# reaction_wheel_board_2017_12_11.net
KiCad netlist of a schematic drawn in EAGLE
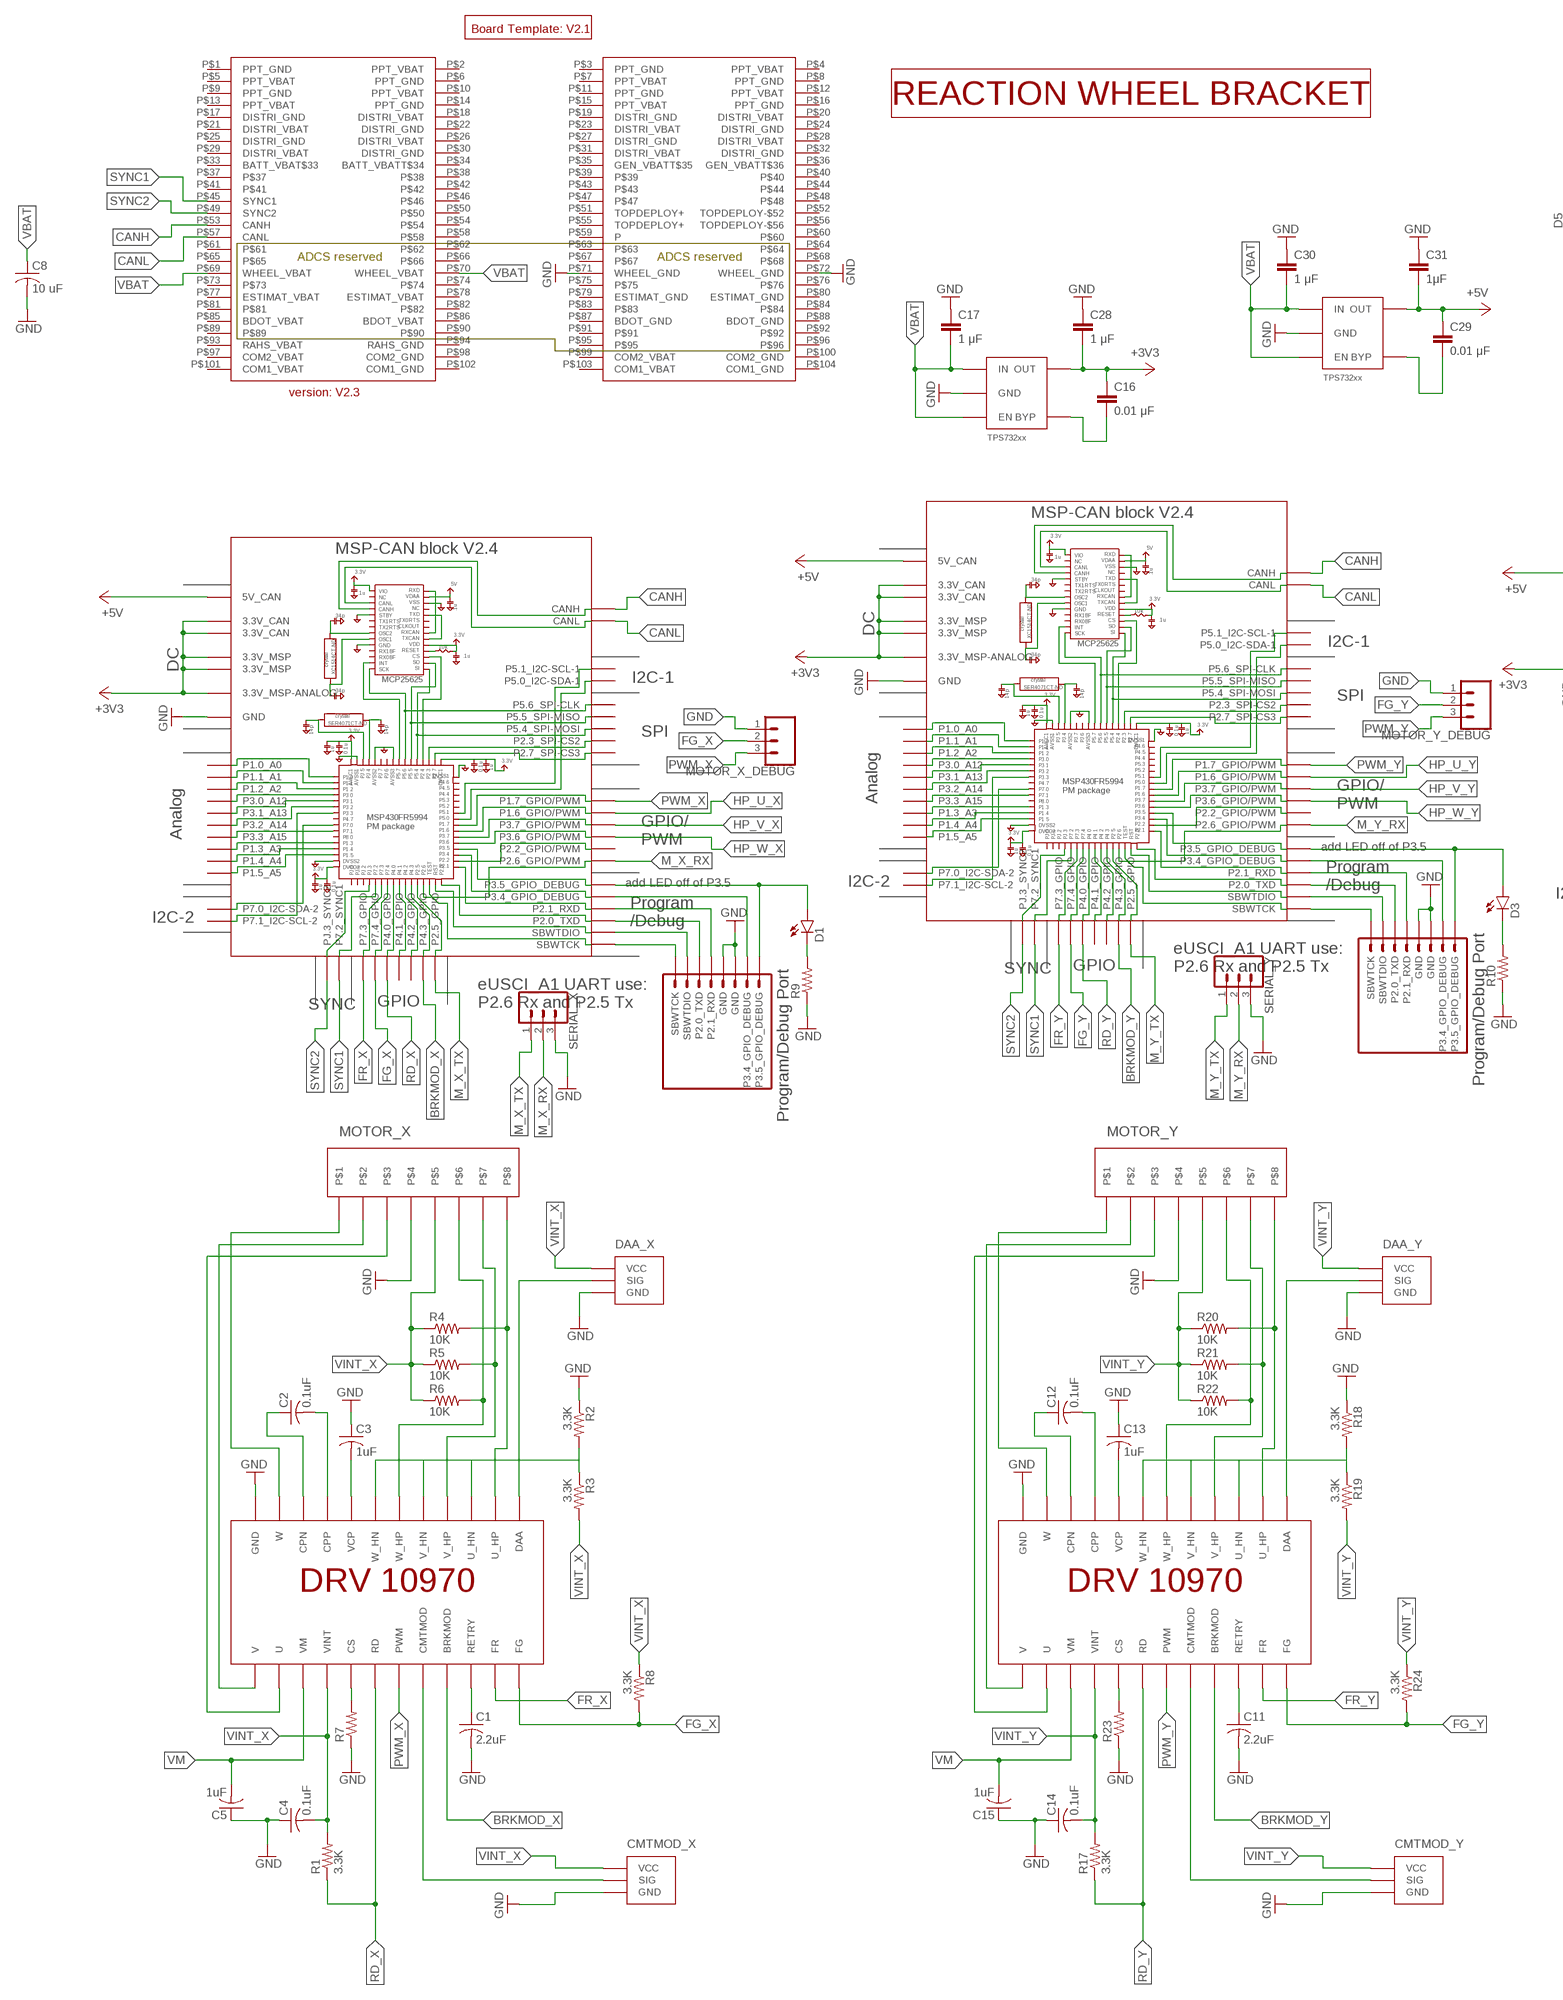
[diagram p0: schematic, sheet 1, part 1 of 2]
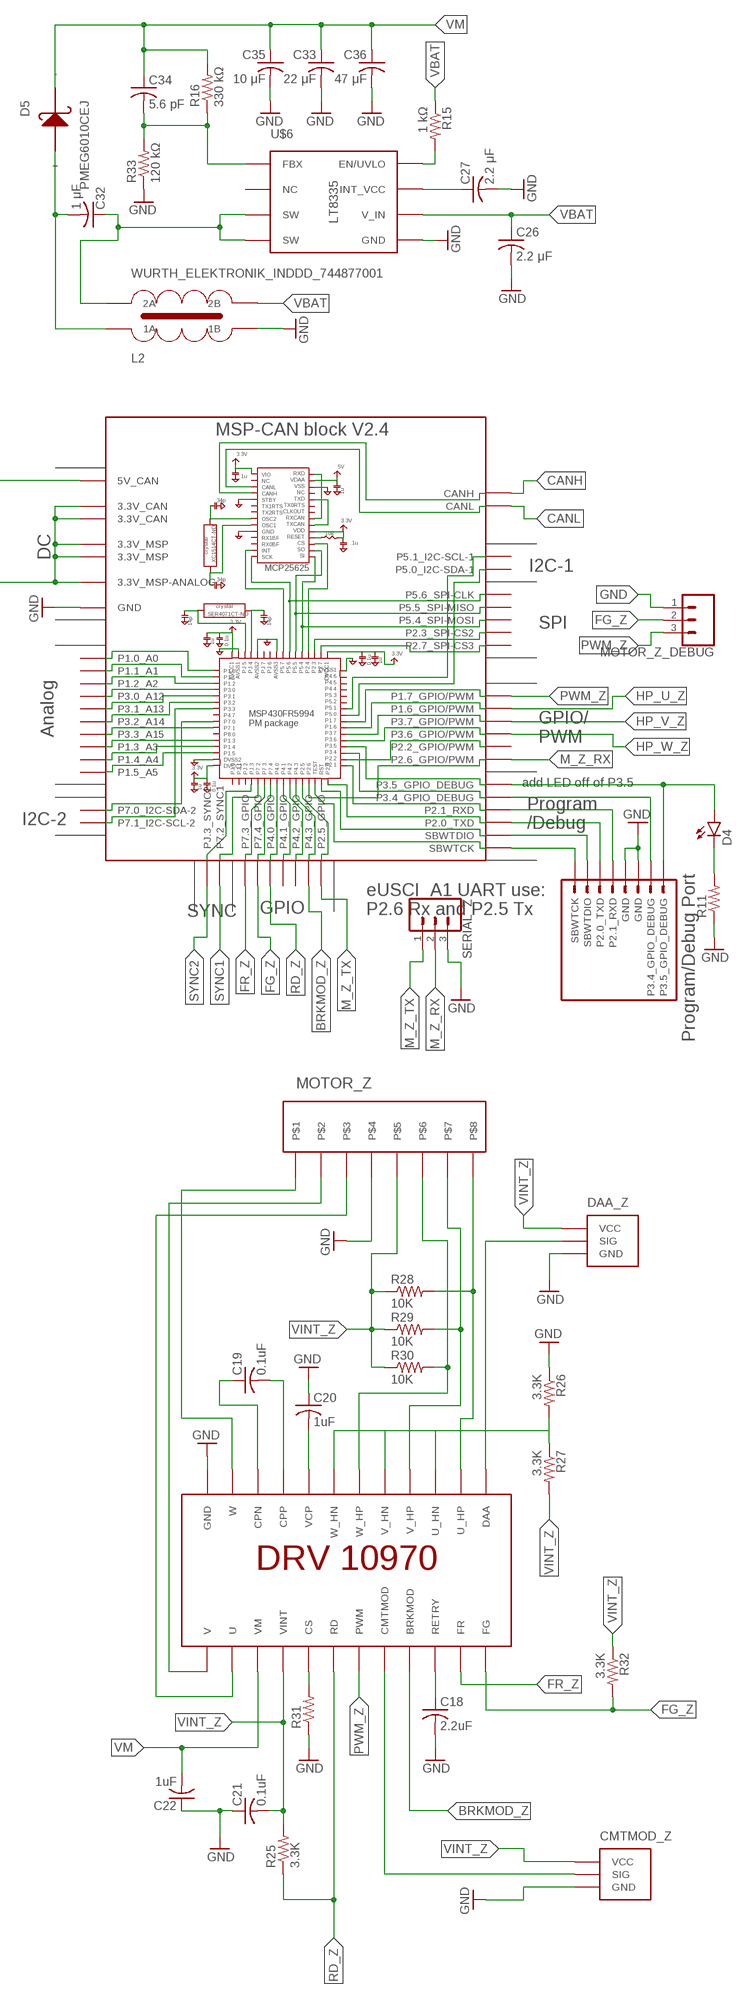
[diagram p1: schematic, sheet 1, part 2 of 2]

(export (version "E")
  (design (tool "Eeschema 10.0.6"))
  (components
    (comp (ref "C1")
      (value "2.2uF")
      (footprint "eagle-import:C1206")
      (libsource (lib "eagle-import") (part "C-USC1206"))
    )
    (comp (ref "C2")
      (value "0.1uF")
      (footprint "eagle-import:C0805")
      (libsource (lib "eagle-import") (part "C-USC0805"))
    )
    (comp (ref "C3")
      (value "1uF")
      (footprint "eagle-import:C1206")
      (libsource (lib "eagle-import") (part "C-USC1206"))
    )
    (comp (ref "C4")
      (value "0.1uF")
      (footprint "eagle-import:C0805")
      (libsource (lib "eagle-import") (part "C-USC0805"))
    )
    (comp (ref "C5")
      (value "1uF")
      (footprint "eagle-import:C1206")
      (libsource (lib "eagle-import") (part "C-USC1206"))
    )
    (comp (ref "C8")
      (value "10 uF")
      (footprint "eagle-import:C0805")
      (libsource (lib "eagle-import") (part "C-USC0805"))
    )
    (comp (ref "C11")
      (value "2.2uF")
      (footprint "eagle-import:C1206")
      (libsource (lib "eagle-import") (part "C-USC1206"))
    )
    (comp (ref "C12")
      (value "0.1uF")
      (footprint "eagle-import:C0805")
      (libsource (lib "eagle-import") (part "C-USC0805"))
    )
    (comp (ref "C13")
      (value "1uF")
      (footprint "eagle-import:C1206")
      (libsource (lib "eagle-import") (part "C-USC1206"))
    )
    (comp (ref "C14")
      (value "0.1uF")
      (footprint "eagle-import:C0805")
      (libsource (lib "eagle-import") (part "C-USC0805"))
    )
    (comp (ref "C15")
      (value "1uF")
      (footprint "eagle-import:C1206")
      (libsource (lib "eagle-import") (part "C-USC1206"))
    )
    (comp (ref "C16")
      (value "0.01 μF")
      (footprint "eagle-import:0805")
      (libsource (lib "eagle-import") (part "CAPACITOR0805"))
    )
    (comp (ref "C17")
      (value "1 μF")
      (footprint "eagle-import:0805")
      (libsource (lib "eagle-import") (part "CAPACITOR0805"))
    )
    (comp (ref "C18")
      (value "2.2uF")
      (footprint "eagle-import:C1206")
      (libsource (lib "eagle-import") (part "C-USC1206"))
    )
    (comp (ref "C19")
      (value "0.1uF")
      (footprint "eagle-import:C0805")
      (libsource (lib "eagle-import") (part "C-USC0805"))
    )
    (comp (ref "C20")
      (value "1uF")
      (footprint "eagle-import:C1206")
      (libsource (lib "eagle-import") (part "C-USC1206"))
    )
    (comp (ref "C21")
      (value "0.1uF")
      (footprint "eagle-import:C0805")
      (libsource (lib "eagle-import") (part "C-USC0805"))
    )
    (comp (ref "C22")
      (value "1uF")
      (footprint "eagle-import:C1206")
      (libsource (lib "eagle-import") (part "C-USC1206"))
    )
    (comp (ref "C26")
      (value "2.2 μF")
      (footprint "eagle-import:C0805")
      (libsource (lib "eagle-import") (part "C-USC0805"))
    )
    (comp (ref "C27")
      (value "2.2 μF")
      (footprint "eagle-import:C0805")
      (libsource (lib "eagle-import") (part "C-USC0805"))
    )
    (comp (ref "C28")
      (value "1 μF")
      (footprint "eagle-import:0805")
      (libsource (lib "eagle-import") (part "CAPACITOR0805"))
    )
    (comp (ref "C29")
      (value "0.01 μF")
      (footprint "eagle-import:0805")
      (libsource (lib "eagle-import") (part "CAPACITOR0805"))
    )
    (comp (ref "C30")
      (value "1 μF")
      (footprint "eagle-import:0805")
      (libsource (lib "eagle-import") (part "CAPACITOR0805"))
    )
    (comp (ref "C31")
      (value "1μF")
      (footprint "eagle-import:0805")
      (libsource (lib "eagle-import") (part "CAPACITOR0805"))
    )
    (comp (ref "C32")
      (value "1 μF")
      (footprint "eagle-import:C0805")
      (libsource (lib "eagle-import") (part "C-USC0805"))
    )
    (comp (ref "C33")
      (value "22 μF")
      (footprint "eagle-import:C1206")
      (libsource (lib "eagle-import") (part "C-USC1206"))
    )
    (comp (ref "C34")
      (value "5.6 pF")
      (footprint "eagle-import:C0805")
      (libsource (lib "eagle-import") (part "C-USC0805"))
    )
    (comp (ref "C35")
      (value "10 μF")
      (footprint "eagle-import:C0805")
      (libsource (lib "eagle-import") (part "C-USC0805"))
    )
    (comp (ref "C36")
      (value "47 μF")
      (footprint "eagle-import:C1206")
      (libsource (lib "eagle-import") (part "C-USC1206"))
    )
    (comp (ref "CMTMOD_X")
      (value "0_OHM_JUMPER")
      (footprint "eagle-import:0_OHM_JUMPER")
      (libsource (lib "eagle-import") (part "0_OHM_JUMPER"))
    )
    (comp (ref "CMTMOD_Y")
      (value "0_OHM_JUMPER")
      (footprint "eagle-import:0_OHM_JUMPER")
      (libsource (lib "eagle-import") (part "0_OHM_JUMPER"))
    )
    (comp (ref "CMTMOD_Z")
      (value "0_OHM_JUMPER")
      (footprint "eagle-import:0_OHM_JUMPER")
      (libsource (lib "eagle-import") (part "0_OHM_JUMPER"))
    )
    (comp (ref "D1")
      (value "LED")
      (footprint "eagle-import:LED-1206")
      (libsource (lib "eagle-import") (part "LED"))
    )
    (comp (ref "D3")
      (value "LED")
      (footprint "eagle-import:LED-1206")
      (libsource (lib "eagle-import") (part "LED"))
    )
    (comp (ref "D4")
      (value "LED")
      (footprint "eagle-import:LED-1206")
      (libsource (lib "eagle-import") (part "LED"))
    )
    (comp (ref "D5")
      (value "PMEG6010CEJ")
      (footprint "eagle-import:SC-90")
      (libsource (lib "eagle-import") (part "PMEG6010CEJ"))
    )
    (comp (ref "DAA_X")
      (value "0_OHM_JUMPER")
      (footprint "eagle-import:0_OHM_JUMPER")
      (libsource (lib "eagle-import") (part "0_OHM_JUMPER"))
    )
    (comp (ref "DAA_Y")
      (value "0_OHM_JUMPER")
      (footprint "eagle-import:0_OHM_JUMPER")
      (libsource (lib "eagle-import") (part "0_OHM_JUMPER"))
    )
    (comp (ref "DAA_Z")
      (value "0_OHM_JUMPER")
      (footprint "eagle-import:0_OHM_JUMPER")
      (libsource (lib "eagle-import") (part "0_OHM_JUMPER"))
    )
    (comp (ref "L2")
      (value "WURTH_ELEKTRONIK_INDDD_744877001")
      (footprint "eagle-import:WURTH_ELEKTRONIK_INDDD_744877001")
      (libsource (lib "eagle-import") (part "WURTH_ELEKTRONIK_INDDD_744877001"))
    )
    (comp (ref "MOTOR_X")
      (value "PICOLOCK_8")
      (footprint "eagle-import:PICOLOCK_8")
      (libsource (lib "eagle-import") (part "PICOLOCK_8"))
    )
    (comp (ref "MOTOR_X_DEBUG")
      (value "CONN_03LOCK")
      (footprint "eagle-import:1X03_LOCK")
      (libsource (lib "eagle-import") (part "CONN_03LOCK"))
    )
    (comp (ref "MOTOR_Y")
      (value "PICOLOCK_8")
      (footprint "eagle-import:PICOLOCK_8")
      (libsource (lib "eagle-import") (part "PICOLOCK_8"))
    )
    (comp (ref "MOTOR_Y_DEBUG")
      (value "CONN_03LOCK")
      (footprint "eagle-import:1X03_LOCK")
      (libsource (lib "eagle-import") (part "CONN_03LOCK"))
    )
    (comp (ref "MOTOR_Z")
      (value "PICOLOCK_8")
      (footprint "eagle-import:PICOLOCK_8")
      (libsource (lib "eagle-import") (part "PICOLOCK_8"))
    )
    (comp (ref "MOTOR_Z_DEBUG")
      (value "CONN_03LOCK")
      (footprint "eagle-import:1X03_LOCK")
      (libsource (lib "eagle-import") (part "CONN_03LOCK"))
    )
    (comp (ref "MSP_X_DEBUG")
      (value "PROGRAM/DEBUG_PORT")
      (footprint "eagle-import:1X08_CONNECTOR")
      (libsource (lib "eagle-import") (part "PROGRAM/DEBUG_PORT"))
    )
    (comp (ref "MSP_Y_DEBUG")
      (value "PROGRAM/DEBUG_PORT")
      (footprint "eagle-import:1X08_CONNECTOR")
      (libsource (lib "eagle-import") (part "PROGRAM/DEBUG_PORT"))
    )
    (comp (ref "MSP_Z_DEBUG")
      (value "PROGRAM/DEBUG_PORT")
      (footprint "eagle-import:1X08_CONNECTOR")
      (libsource (lib "eagle-import") (part "PROGRAM/DEBUG_PORT"))
    )
    (comp (ref "PC104")
      (value "PC104_CONNECTOR")
      (footprint "eagle-import:PC104_CONNECTOR")
      (libsource (lib "eagle-import") (part "PC104_CONNECTOR"))
    )
    (comp (ref "R1")
      (value "3.3K")
      (footprint "eagle-import:0805")
      (libsource (lib "eagle-import") (part "RESISTOR0805"))
    )
    (comp (ref "R2")
      (value "3.3K")
      (footprint "eagle-import:0805")
      (libsource (lib "eagle-import") (part "RESISTOR0805"))
    )
    (comp (ref "R3")
      (value "3.3K")
      (footprint "eagle-import:0805")
      (libsource (lib "eagle-import") (part "RESISTOR0805"))
    )
    (comp (ref "R4")
      (value "10K")
      (footprint "eagle-import:0805")
      (libsource (lib "eagle-import") (part "RESISTOR0805"))
    )
    (comp (ref "R5")
      (value "10K")
      (footprint "eagle-import:0805")
      (libsource (lib "eagle-import") (part "RESISTOR0805"))
    )
    (comp (ref "R6")
      (value "10K")
      (footprint "eagle-import:0805")
      (libsource (lib "eagle-import") (part "RESISTOR0805"))
    )
    (comp (ref "R7")
      (value "RESISTOR0805")
      (footprint "eagle-import:0805")
      (libsource (lib "eagle-import") (part "RESISTOR0805"))
    )
    (comp (ref "R8")
      (value "3.3K")
      (footprint "eagle-import:0805")
      (libsource (lib "eagle-import") (part "RESISTOR0805"))
    )
    (comp (ref "R9")
      (value "RESISTOR0805")
      (footprint "eagle-import:0805")
      (libsource (lib "eagle-import") (part "RESISTOR0805"))
    )
    (comp (ref "R10")
      (value "RESISTOR0805")
      (footprint "eagle-import:0805")
      (libsource (lib "eagle-import") (part "RESISTOR0805"))
    )
    (comp (ref "R11")
      (value "RESISTOR0805")
      (footprint "eagle-import:0805")
      (libsource (lib "eagle-import") (part "RESISTOR0805"))
    )
    (comp (ref "R15")
      (value "1 kΩ")
      (footprint "eagle-import:0805")
      (libsource (lib "eagle-import") (part "RESISTOR0805"))
    )
    (comp (ref "R16")
      (value "330 kΩ")
      (footprint "eagle-import:0805")
      (libsource (lib "eagle-import") (part "RESISTOR0805"))
    )
    (comp (ref "R17")
      (value "3.3K")
      (footprint "eagle-import:0805")
      (libsource (lib "eagle-import") (part "RESISTOR0805"))
    )
    (comp (ref "R18")
      (value "3.3K")
      (footprint "eagle-import:0805")
      (libsource (lib "eagle-import") (part "RESISTOR0805"))
    )
    (comp (ref "R19")
      (value "3.3K")
      (footprint "eagle-import:0805")
      (libsource (lib "eagle-import") (part "RESISTOR0805"))
    )
    (comp (ref "R20")
      (value "10K")
      (footprint "eagle-import:0805")
      (libsource (lib "eagle-import") (part "RESISTOR0805"))
    )
    (comp (ref "R21")
      (value "10K")
      (footprint "eagle-import:0805")
      (libsource (lib "eagle-import") (part "RESISTOR0805"))
    )
    (comp (ref "R22")
      (value "10K")
      (footprint "eagle-import:0805")
      (libsource (lib "eagle-import") (part "RESISTOR0805"))
    )
    (comp (ref "R23")
      (value "RESISTOR0805")
      (footprint "eagle-import:0805")
      (libsource (lib "eagle-import") (part "RESISTOR0805"))
    )
    (comp (ref "R24")
      (value "3.3K")
      (footprint "eagle-import:0805")
      (libsource (lib "eagle-import") (part "RESISTOR0805"))
    )
    (comp (ref "R25")
      (value "3.3K")
      (footprint "eagle-import:0805")
      (libsource (lib "eagle-import") (part "RESISTOR0805"))
    )
    (comp (ref "R26")
      (value "3.3K")
      (footprint "eagle-import:0805")
      (libsource (lib "eagle-import") (part "RESISTOR0805"))
    )
    (comp (ref "R27")
      (value "3.3K")
      (footprint "eagle-import:0805")
      (libsource (lib "eagle-import") (part "RESISTOR0805"))
    )
    (comp (ref "R28")
      (value "10K")
      (footprint "eagle-import:0805")
      (libsource (lib "eagle-import") (part "RESISTOR0805"))
    )
    (comp (ref "R29")
      (value "10K")
      (footprint "eagle-import:0805")
      (libsource (lib "eagle-import") (part "RESISTOR0805"))
    )
    (comp (ref "R30")
      (value "10K")
      (footprint "eagle-import:0805")
      (libsource (lib "eagle-import") (part "RESISTOR0805"))
    )
    (comp (ref "R31")
      (value "RESISTOR0805")
      (footprint "eagle-import:0805")
      (libsource (lib "eagle-import") (part "RESISTOR0805"))
    )
    (comp (ref "R32")
      (value "3.3K")
      (footprint "eagle-import:0805")
      (libsource (lib "eagle-import") (part "RESISTOR0805"))
    )
    (comp (ref "R33")
      (value "120 kΩ")
      (footprint "eagle-import:0805")
      (libsource (lib "eagle-import") (part "RESISTOR0805"))
    )
    (comp (ref "SERIAL_X")
      (value "CONN_03LOCK")
      (footprint "eagle-import:1X03_LOCK")
      (libsource (lib "eagle-import") (part "CONN_03LOCK"))
    )
    (comp (ref "SERIAL_Y")
      (value "CONN_03LOCK")
      (footprint "eagle-import:1X03_LOCK")
      (libsource (lib "eagle-import") (part "CONN_03LOCK"))
    )
    (comp (ref "SERIAL_Z")
      (value "CONN_03LOCK")
      (footprint "eagle-import:1X03_LOCK")
      (libsource (lib "eagle-import") (part "CONN_03LOCK"))
    )
    (comp (ref "U$1")
      (value "BOARD_TEMPLATESERCURED")
      (footprint "eagle-import:BOARD_TEMPLATE_SECURED")
      (libsource (lib "eagle-import") (part "BOARD_TEMPLATESERCURED"))
    )
    (comp (ref "U$3")
      (value "MSP-CAN_BLOCK")
      (footprint "eagle-import:MSP-CAN_BLOCK")
      (libsource (lib "eagle-import") (part "MSP-CAN_BLOCK"))
    )
    (comp (ref "U$6")
      (value "LT8335")
      (footprint "eagle-import:DDB")
      (libsource (lib "eagle-import") (part "LT8335"))
    )
    (comp (ref "U$7")
      (value "DRV10970")
      (footprint "eagle-import:DRV10970")
      (libsource (lib "eagle-import") (part "DRV10970"))
    )
    (comp (ref "U$9")
      (value "REACTION_WHEEL_BRACKET")
      (footprint "eagle-import:REACTION_WHEEL_BRACKET")
      (libsource (lib "eagle-import") (part "REACTION_WHEEL_BRACKET"))
    )
    (comp (ref "U$10")
      (value "MSP-CAN_BLOCK")
      (footprint "eagle-import:MSP-CAN_BLOCK")
      (libsource (lib "eagle-import") (part "MSP-CAN_BLOCK"))
    )
    (comp (ref "U$12")
      (value "DRV10970")
      (footprint "eagle-import:DRV10970")
      (libsource (lib "eagle-import") (part "DRV10970"))
    )
    (comp (ref "U$13")
      (value "MSP-CAN_BLOCK")
      (footprint "eagle-import:MSP-CAN_BLOCK")
      (libsource (lib "eagle-import") (part "MSP-CAN_BLOCK"))
    )
    (comp (ref "U$15")
      (value "DRV10970")
      (footprint "eagle-import:DRV10970")
      (libsource (lib "eagle-import") (part "DRV10970"))
    )
    (comp (ref "U2")
      (value "TPS732XX")
      (footprint "eagle-import:SOT-23-5")
      (libsource (lib "eagle-import") (part "TPS732XX"))
    )
    (comp (ref "U3")
      (value "TPS732XX")
      (footprint "eagle-import:SOT-23-5")
      (libsource (lib "eagle-import") (part "TPS732XX"))
    )
  )
  (nets
    (net (code "1") (name "+3V3") (class "Default")
      (node (ref "C16") (pin "1") (pinfunction "1_1") (pintype "passive"))
      (node (ref "C28") (pin "2") (pinfunction "2_2") (pintype "passive"))
      (node (ref "U$10") (pin "3.3V@CAN1") (pinfunction "3.3V_CAN_3.3V@CAN1") (pintype "bidirectional"))
      (node (ref "U$10") (pin "3.3V@CAN2") (pinfunction "3.3V_CAN_3.3V@CAN2") (pintype "bidirectional"))
      (node (ref "U$10") (pin "3.3V@MSP1") (pinfunction "3.3V_MSP_3.3V@MSP1") (pintype "bidirectional"))
      (node (ref "U$10") (pin "3.3V@MSP2") (pinfunction "3.3V_MSP_3.3V@MSP2") (pintype "bidirectional"))
      (node (ref "U$10") (pin "3.3V_ANALOG@MSP2") (pinfunction "3.3V_MSP-ANALOG_3.3V_ANALOG@MSP2") (pintype "bidirectional"))
      (node (ref "U$13") (pin "3.3V@CAN1") (pinfunction "3.3V_CAN_3.3V@CAN1") (pintype "bidirectional"))
      (node (ref "U$13") (pin "3.3V@CAN2") (pinfunction "3.3V_CAN_3.3V@CAN2") (pintype "bidirectional"))
      (node (ref "U$13") (pin "3.3V@MSP1") (pinfunction "3.3V_MSP_3.3V@MSP1") (pintype "bidirectional"))
      (node (ref "U$13") (pin "3.3V@MSP2") (pinfunction "3.3V_MSP_3.3V@MSP2") (pintype "bidirectional"))
      (node (ref "U$13") (pin "3.3V_ANALOG@MSP2") (pinfunction "3.3V_MSP-ANALOG_3.3V_ANALOG@MSP2") (pintype "bidirectional"))
      (node (ref "U$3") (pin "3.3V@CAN1") (pinfunction "3.3V_CAN_3.3V@CAN1") (pintype "bidirectional"))
      (node (ref "U$3") (pin "3.3V@CAN2") (pinfunction "3.3V_CAN_3.3V@CAN2") (pintype "bidirectional"))
      (node (ref "U$3") (pin "3.3V@MSP1") (pinfunction "3.3V_MSP_3.3V@MSP1") (pintype "bidirectional"))
      (node (ref "U$3") (pin "3.3V@MSP2") (pinfunction "3.3V_MSP_3.3V@MSP2") (pintype "bidirectional"))
      (node (ref "U$3") (pin "3.3V_ANALOG@MSP2") (pinfunction "3.3V_MSP-ANALOG_3.3V_ANALOG@MSP2") (pintype "bidirectional"))
      (node (ref "U2") (pin "P$5") (pinfunction "OUT_P$5") (pintype "bidirectional"))
    )
    (net (code "2") (name "+5V") (class "Default")
      (node (ref "C29") (pin "1") (pinfunction "1_1") (pintype "passive"))
      (node (ref "C31") (pin "2") (pinfunction "2_2") (pintype "passive"))
      (node (ref "U$10") (pin "5V") (pinfunction "5V_CAN_5V") (pintype "bidirectional"))
      (node (ref "U$13") (pin "5V") (pinfunction "5V_CAN_5V") (pintype "bidirectional"))
      (node (ref "U$3") (pin "5V") (pinfunction "5V_CAN_5V") (pintype "bidirectional"))
      (node (ref "U3") (pin "P$5") (pinfunction "OUT_P$5") (pintype "bidirectional"))
    )
    (net (code "3") (name "BRKMOD_X") (class "Default")
      (node (ref "U$3") (pin "P4.3_GPIO") (pinfunction "P4.3_GPIO_P4.3_GPIO") (pintype "bidirectional"))
      (node (ref "U$7") (pin "BRKMOD") (pinfunction "BRKMOD_BRKMOD") (pintype "bidirectional"))
    )
    (net (code "4") (name "BRKMOD_Y") (class "Default")
      (node (ref "U$10") (pin "P4.3_GPIO") (pinfunction "P4.3_GPIO_P4.3_GPIO") (pintype "bidirectional"))
      (node (ref "U$12") (pin "BRKMOD") (pinfunction "BRKMOD_BRKMOD") (pintype "bidirectional"))
    )
    (net (code "5") (name "BRKMOD_Z") (class "Default")
      (node (ref "U$13") (pin "P4.3_GPIO") (pinfunction "P4.3_GPIO_P4.3_GPIO") (pintype "bidirectional"))
      (node (ref "U$15") (pin "BRKMOD") (pinfunction "BRKMOD_BRKMOD") (pintype "bidirectional"))
    )
    (net (code "6") (name "CANH") (class "Default")
      (node (ref "PC104") (pin "P$53") (pinfunction "CANH_P$53") (pintype "bidirectional"))
      (node (ref "U$10") (pin "CANH") (pinfunction "CANH_CANH") (pintype "bidirectional"))
      (node (ref "U$13") (pin "CANH") (pinfunction "CANH_CANH") (pintype "bidirectional"))
      (node (ref "U$3") (pin "CANH") (pinfunction "CANH_CANH") (pintype "bidirectional"))
    )
    (net (code "7") (name "CANL") (class "Default")
      (node (ref "PC104") (pin "P$57") (pinfunction "CANL_P$57") (pintype "bidirectional"))
      (node (ref "U$10") (pin "CANL") (pinfunction "CANL_CANL") (pintype "bidirectional"))
      (node (ref "U$13") (pin "CANL") (pinfunction "CANL_CANL") (pintype "bidirectional"))
      (node (ref "U$3") (pin "CANL") (pinfunction "CANL_CANL") (pintype "bidirectional"))
    )
    (net (code "8") (name "FG_X") (class "Default")
      (node (ref "MOTOR_X_DEBUG") (pin "2") (pinfunction "2_2") (pintype "passive"))
      (node (ref "R8") (pin "2") (pinfunction "2_2") (pintype "passive"))
      (node (ref "U$3") (pin "P7.4_GPIO") (pinfunction "P7.4_GPIO_P7.4_GPIO") (pintype "bidirectional"))
      (node (ref "U$7") (pin "FG") (pinfunction "FG_FG") (pintype "bidirectional"))
    )
    (net (code "9") (name "FG_Y") (class "Default")
      (node (ref "MOTOR_Y_DEBUG") (pin "2") (pinfunction "2_2") (pintype "passive"))
      (node (ref "R24") (pin "2") (pinfunction "2_2") (pintype "passive"))
      (node (ref "U$10") (pin "P7.4_GPIO") (pinfunction "P7.4_GPIO_P7.4_GPIO") (pintype "bidirectional"))
      (node (ref "U$12") (pin "FG") (pinfunction "FG_FG") (pintype "bidirectional"))
    )
    (net (code "10") (name "FG_Z") (class "Default")
      (node (ref "MOTOR_Z_DEBUG") (pin "2") (pinfunction "2_2") (pintype "passive"))
      (node (ref "R32") (pin "2") (pinfunction "2_2") (pintype "passive"))
      (node (ref "U$13") (pin "P7.4_GPIO") (pinfunction "P7.4_GPIO_P7.4_GPIO") (pintype "bidirectional"))
      (node (ref "U$15") (pin "FG") (pinfunction "FG_FG") (pintype "bidirectional"))
    )
    (net (code "11") (name "FR_X") (class "Default")
      (node (ref "U$3") (pin "P7.3_GPIO") (pinfunction "P7.3_GPIO_P7.3_GPIO") (pintype "bidirectional"))
      (node (ref "U$7") (pin "FR") (pinfunction "FR_FR") (pintype "bidirectional"))
    )
    (net (code "12") (name "FR_Y") (class "Default")
      (node (ref "U$10") (pin "P7.3_GPIO") (pinfunction "P7.3_GPIO_P7.3_GPIO") (pintype "bidirectional"))
      (node (ref "U$12") (pin "FR") (pinfunction "FR_FR") (pintype "bidirectional"))
    )
    (net (code "13") (name "FR_Z") (class "Default")
      (node (ref "U$13") (pin "P7.3_GPIO") (pinfunction "P7.3_GPIO_P7.3_GPIO") (pintype "bidirectional"))
      (node (ref "U$15") (pin "FR") (pinfunction "FR_FR") (pintype "bidirectional"))
    )
    (net (code "14") (name "GND") (class "Default")
      (node (ref "C1") (pin "2") (pinfunction "2_2") (pintype "passive"))
      (node (ref "C11") (pin "2") (pinfunction "2_2") (pintype "passive"))
      (node (ref "C13") (pin "1") (pinfunction "1_1") (pintype "passive"))
      (node (ref "C14") (pin "1") (pinfunction "1_1") (pintype "passive"))
      (node (ref "C15") (pin "1") (pinfunction "1_1") (pintype "passive"))
      (node (ref "C17") (pin "1") (pinfunction "1_1") (pintype "passive"))
      (node (ref "C18") (pin "2") (pinfunction "2_2") (pintype "passive"))
      (node (ref "C20") (pin "1") (pinfunction "1_1") (pintype "passive"))
      (node (ref "C21") (pin "1") (pinfunction "1_1") (pintype "passive"))
      (node (ref "C22") (pin "1") (pinfunction "1_1") (pintype "passive"))
      (node (ref "C26") (pin "2") (pinfunction "2_2") (pintype "passive"))
      (node (ref "C27") (pin "2") (pinfunction "2_2") (pintype "passive"))
      (node (ref "C28") (pin "1") (pinfunction "1_1") (pintype "passive"))
      (node (ref "C3") (pin "1") (pinfunction "1_1") (pintype "passive"))
      (node (ref "C30") (pin "1") (pinfunction "1_1") (pintype "passive"))
      (node (ref "C31") (pin "1") (pinfunction "1_1") (pintype "passive"))
      (node (ref "C33") (pin "2") (pinfunction "2_2") (pintype "passive"))
      (node (ref "C35") (pin "2") (pinfunction "2_2") (pintype "passive"))
      (node (ref "C36") (pin "2") (pinfunction "2_2") (pintype "passive"))
      (node (ref "C4") (pin "1") (pinfunction "1_1") (pintype "passive"))
      (node (ref "C5") (pin "1") (pinfunction "1_1") (pintype "passive"))
      (node (ref "C8") (pin "2") (pinfunction "2_2") (pintype "passive"))
      (node (ref "CMTMOD_X") (pin "P$1") (pinfunction "GND_P$1") (pintype "bidirectional"))
      (node (ref "CMTMOD_Y") (pin "P$1") (pinfunction "GND_P$1") (pintype "bidirectional"))
      (node (ref "CMTMOD_Z") (pin "P$1") (pinfunction "GND_P$1") (pintype "bidirectional"))
      (node (ref "DAA_X") (pin "P$1") (pinfunction "GND_P$1") (pintype "bidirectional"))
      (node (ref "DAA_Y") (pin "P$1") (pinfunction "GND_P$1") (pintype "bidirectional"))
      (node (ref "DAA_Z") (pin "P$1") (pinfunction "GND_P$1") (pintype "bidirectional"))
      (node (ref "L2") (pin "P$2") (pinfunction "1B_P$2") (pintype "bidirectional"))
      (node (ref "MOTOR_X") (pin "P$4") (pinfunction "P$4_P$4") (pintype "bidirectional"))
      (node (ref "MOTOR_X_DEBUG") (pin "1") (pinfunction "1_1") (pintype "passive"))
      (node (ref "MOTOR_Y") (pin "P$4") (pinfunction "P$4_P$4") (pintype "bidirectional"))
      (node (ref "MOTOR_Y_DEBUG") (pin "1") (pinfunction "1_1") (pintype "passive"))
      (node (ref "MOTOR_Z") (pin "P$4") (pinfunction "P$4_P$4") (pintype "bidirectional"))
      (node (ref "MOTOR_Z_DEBUG") (pin "1") (pinfunction "1_1") (pintype "passive"))
      (node (ref "MSP_X_DEBUG") (pin "5") (pinfunction "GND_5") (pintype "bidirectional"))
      (node (ref "MSP_X_DEBUG") (pin "6") (pinfunction "GND_6") (pintype "bidirectional"))
      (node (ref "MSP_Y_DEBUG") (pin "5") (pinfunction "GND_5") (pintype "bidirectional"))
      (node (ref "MSP_Y_DEBUG") (pin "6") (pinfunction "GND_6") (pintype "bidirectional"))
      (node (ref "MSP_Z_DEBUG") (pin "5") (pinfunction "GND_5") (pintype "bidirectional"))
      (node (ref "MSP_Z_DEBUG") (pin "6") (pinfunction "GND_6") (pintype "bidirectional"))
      (node (ref "PC104") (pin "P$71") (pinfunction "WHEEL_GND_P$71") (pintype "bidirectional"))
      (node (ref "PC104") (pin "P$72") (pinfunction "WHEEL_GND_P$72") (pintype "bidirectional"))
      (node (ref "R10") (pin "1") (pinfunction "1_1") (pintype "passive"))
      (node (ref "R11") (pin "1") (pinfunction "1_1") (pintype "passive"))
      (node (ref "R18") (pin "1") (pinfunction "1_1") (pintype "passive"))
      (node (ref "R2") (pin "1") (pinfunction "1_1") (pintype "passive"))
      (node (ref "R23") (pin "1") (pinfunction "1_1") (pintype "passive"))
      (node (ref "R26") (pin "1") (pinfunction "1_1") (pintype "passive"))
      (node (ref "R31") (pin "1") (pinfunction "1_1") (pintype "passive"))
      (node (ref "R33") (pin "1") (pinfunction "1_1") (pintype "passive"))
      (node (ref "R7") (pin "1") (pinfunction "1_1") (pintype "passive"))
      (node (ref "R9") (pin "1") (pinfunction "1_1") (pintype "passive"))
      (node (ref "SERIAL_X") (pin "3") (pinfunction "3_3") (pintype "passive"))
      (node (ref "SERIAL_Y") (pin "3") (pinfunction "3_3") (pintype "passive"))
      (node (ref "SERIAL_Z") (pin "3") (pinfunction "3_3") (pintype "passive"))
      (node (ref "U$10") (pin "GND@1") (pinfunction "GND_GND@1") (pintype "bidirectional"))
      (node (ref "U$10") (pin "GND@10") (pinfunction "GND_GND@10") (pintype "bidirectional"))
      (node (ref "U$10") (pin "GND@11") (pinfunction "GND_GND@11") (pintype "bidirectional"))
      (node (ref "U$10") (pin "GND@12") (pinfunction "GND_GND@12") (pintype "bidirectional"))
      (node (ref "U$10") (pin "GND@13") (pinfunction "GND_GND@13") (pintype "bidirectional"))
      (node (ref "U$10") (pin "GND@14") (pinfunction "GND_GND@14") (pintype "bidirectional"))
      (node (ref "U$10") (pin "GND@15") (pinfunction "GND_GND@15") (pintype "bidirectional"))
      (node (ref "U$10") (pin "GND@16") (pinfunction "GND_GND@16") (pintype "bidirectional"))
      (node (ref "U$10") (pin "GND@17") (pinfunction "GND_GND@17") (pintype "bidirectional"))
      (node (ref "U$10") (pin "GND@2") (pinfunction "GND_GND@2") (pintype "bidirectional"))
      (node (ref "U$10") (pin "GND@26") (pinfunction "GND_GND@26") (pintype "bidirectional"))
      (node (ref "U$10") (pin "GND@3") (pinfunction "GND_GND@3") (pintype "bidirectional"))
      (node (ref "U$10") (pin "GND@4") (pinfunction "GND_GND@4") (pintype "bidirectional"))
      (node (ref "U$10") (pin "GND@5") (pinfunction "GND_GND@5") (pintype "bidirectional"))
      (node (ref "U$10") (pin "GND@7") (pinfunction "GND_GND@7") (pintype "bidirectional"))
      (node (ref "U$10") (pin "GND@8") (pinfunction "GND_GND@8") (pintype "bidirectional"))
      (node (ref "U$10") (pin "GND@9") (pinfunction "GND_GND@9") (pintype "bidirectional"))
      (node (ref "U$12") (pin "GND@1") (pinfunction "GND_GND@1") (pintype "bidirectional"))
      (node (ref "U$12") (pin "GND@2") (pinfunction "GND_GND@2") (pintype "bidirectional"))
      (node (ref "U$13") (pin "GND@1") (pinfunction "GND_GND@1") (pintype "bidirectional"))
      (node (ref "U$13") (pin "GND@10") (pinfunction "GND_GND@10") (pintype "bidirectional"))
      (node (ref "U$13") (pin "GND@11") (pinfunction "GND_GND@11") (pintype "bidirectional"))
      (node (ref "U$13") (pin "GND@12") (pinfunction "GND_GND@12") (pintype "bidirectional"))
      (node (ref "U$13") (pin "GND@13") (pinfunction "GND_GND@13") (pintype "bidirectional"))
      (node (ref "U$13") (pin "GND@14") (pinfunction "GND_GND@14") (pintype "bidirectional"))
      (node (ref "U$13") (pin "GND@15") (pinfunction "GND_GND@15") (pintype "bidirectional"))
      (node (ref "U$13") (pin "GND@16") (pinfunction "GND_GND@16") (pintype "bidirectional"))
      (node (ref "U$13") (pin "GND@17") (pinfunction "GND_GND@17") (pintype "bidirectional"))
      (node (ref "U$13") (pin "GND@2") (pinfunction "GND_GND@2") (pintype "bidirectional"))
      (node (ref "U$13") (pin "GND@26") (pinfunction "GND_GND@26") (pintype "bidirectional"))
      (node (ref "U$13") (pin "GND@3") (pinfunction "GND_GND@3") (pintype "bidirectional"))
      (node (ref "U$13") (pin "GND@4") (pinfunction "GND_GND@4") (pintype "bidirectional"))
      (node (ref "U$13") (pin "GND@5") (pinfunction "GND_GND@5") (pintype "bidirectional"))
      (node (ref "U$13") (pin "GND@7") (pinfunction "GND_GND@7") (pintype "bidirectional"))
      (node (ref "U$13") (pin "GND@8") (pinfunction "GND_GND@8") (pintype "bidirectional"))
      (node (ref "U$13") (pin "GND@9") (pinfunction "GND_GND@9") (pintype "bidirectional"))
      (node (ref "U$15") (pin "GND@1") (pinfunction "GND_GND@1") (pintype "bidirectional"))
      (node (ref "U$15") (pin "GND@2") (pinfunction "GND_GND@2") (pintype "bidirectional"))
      (node (ref "U$3") (pin "GND@1") (pinfunction "GND_GND@1") (pintype "bidirectional"))
      (node (ref "U$3") (pin "GND@10") (pinfunction "GND_GND@10") (pintype "bidirectional"))
      (node (ref "U$3") (pin "GND@11") (pinfunction "GND_GND@11") (pintype "bidirectional"))
      (node (ref "U$3") (pin "GND@12") (pinfunction "GND_GND@12") (pintype "bidirectional"))
      (node (ref "U$3") (pin "GND@13") (pinfunction "GND_GND@13") (pintype "bidirectional"))
      (node (ref "U$3") (pin "GND@14") (pinfunction "GND_GND@14") (pintype "bidirectional"))
      (node (ref "U$3") (pin "GND@15") (pinfunction "GND_GND@15") (pintype "bidirectional"))
      (node (ref "U$3") (pin "GND@16") (pinfunction "GND_GND@16") (pintype "bidirectional"))
      (node (ref "U$3") (pin "GND@17") (pinfunction "GND_GND@17") (pintype "bidirectional"))
      (node (ref "U$3") (pin "GND@2") (pinfunction "GND_GND@2") (pintype "bidirectional"))
      (node (ref "U$3") (pin "GND@26") (pinfunction "GND_GND@26") (pintype "bidirectional"))
      (node (ref "U$3") (pin "GND@3") (pinfunction "GND_GND@3") (pintype "bidirectional"))
      (node (ref "U$3") (pin "GND@4") (pinfunction "GND_GND@4") (pintype "bidirectional"))
      (node (ref "U$3") (pin "GND@5") (pinfunction "GND_GND@5") (pintype "bidirectional"))
      (node (ref "U$3") (pin "GND@7") (pinfunction "GND_GND@7") (pintype "bidirectional"))
      (node (ref "U$3") (pin "GND@8") (pinfunction "GND_GND@8") (pintype "bidirectional"))
      (node (ref "U$3") (pin "GND@9") (pinfunction "GND_GND@9") (pintype "bidirectional"))
      (node (ref "U$6") (pin "GND") (pinfunction "GND_GND") (pintype "bidirectional"))
      (node (ref "U$6") (pin "P$5") (pinfunction "GND_P$5") (pintype "bidirectional"))
      (node (ref "U$7") (pin "GND@1") (pinfunction "GND_GND@1") (pintype "bidirectional"))
      (node (ref "U$7") (pin "GND@2") (pinfunction "GND_GND@2") (pintype "bidirectional"))
      (node (ref "U2") (pin "P$2") (pinfunction "GND_P$2") (pintype "bidirectional"))
      (node (ref "U3") (pin "P$2") (pinfunction "GND_P$2") (pintype "bidirectional"))
    )
    (net (code "15") (name "HP_U_X") (class "Default")
      (node (ref "MOTOR_X") (pin "P$8") (pinfunction "P$8_P$8") (pintype "bidirectional"))
      (node (ref "R4") (pin "2") (pinfunction "2_2") (pintype "passive"))
      (node (ref "U$3") (pin "P1.6_GPIO/PWM") (pinfunction "P1.6_GPIO/PWM_P1.6_GPIO/PWM") (pintype "bidirectional"))
      (node (ref "U$7") (pin "U_HP") (pinfunction "U_HP_U_HP") (pintype "bidirectional"))
    )
    (net (code "16") (name "HP_U_Y") (class "Default")
      (node (ref "MOTOR_Y") (pin "P$8") (pinfunction "P$8_P$8") (pintype "bidirectional"))
      (node (ref "R20") (pin "2") (pinfunction "2_2") (pintype "passive"))
      (node (ref "U$10") (pin "P1.6_GPIO/PWM") (pinfunction "P1.6_GPIO/PWM_P1.6_GPIO/PWM") (pintype "bidirectional"))
      (node (ref "U$12") (pin "U_HP") (pinfunction "U_HP_U_HP") (pintype "bidirectional"))
    )
    (net (code "17") (name "HP_U_Z") (class "Default")
      (node (ref "MOTOR_Z") (pin "P$8") (pinfunction "P$8_P$8") (pintype "bidirectional"))
      (node (ref "R28") (pin "2") (pinfunction "2_2") (pintype "passive"))
      (node (ref "U$13") (pin "P1.6_GPIO/PWM") (pinfunction "P1.6_GPIO/PWM_P1.6_GPIO/PWM") (pintype "bidirectional"))
      (node (ref "U$15") (pin "U_HP") (pinfunction "U_HP_U_HP") (pintype "bidirectional"))
    )
    (net (code "18") (name "HP_V_X") (class "Default")
      (node (ref "MOTOR_X") (pin "P$7") (pinfunction "P$7_P$7") (pintype "bidirectional"))
      (node (ref "R5") (pin "2") (pinfunction "2_2") (pintype "passive"))
      (node (ref "U$3") (pin "P3.7_GPIO/PWM") (pinfunction "P3.7_GPIO/PWM_P3.7_GPIO/PWM") (pintype "bidirectional"))
      (node (ref "U$7") (pin "V_HP") (pinfunction "V_HP_V_HP") (pintype "bidirectional"))
    )
    (net (code "19") (name "HP_V_Y") (class "Default")
      (node (ref "MOTOR_Y") (pin "P$7") (pinfunction "P$7_P$7") (pintype "bidirectional"))
      (node (ref "R21") (pin "2") (pinfunction "2_2") (pintype "passive"))
      (node (ref "U$10") (pin "P3.7_GPIO/PWM") (pinfunction "P3.7_GPIO/PWM_P3.7_GPIO/PWM") (pintype "bidirectional"))
      (node (ref "U$12") (pin "V_HP") (pinfunction "V_HP_V_HP") (pintype "bidirectional"))
    )
    (net (code "20") (name "HP_V_Z") (class "Default")
      (node (ref "MOTOR_Z") (pin "P$7") (pinfunction "P$7_P$7") (pintype "bidirectional"))
      (node (ref "R29") (pin "2") (pinfunction "2_2") (pintype "passive"))
      (node (ref "U$13") (pin "P3.7_GPIO/PWM") (pinfunction "P3.7_GPIO/PWM_P3.7_GPIO/PWM") (pintype "bidirectional"))
      (node (ref "U$15") (pin "V_HP") (pinfunction "V_HP_V_HP") (pintype "bidirectional"))
    )
    (net (code "21") (name "HP_W_X") (class "Default")
      (node (ref "MOTOR_X") (pin "P$6") (pinfunction "P$6_P$6") (pintype "bidirectional"))
      (node (ref "R6") (pin "2") (pinfunction "2_2") (pintype "passive"))
      (node (ref "U$3") (pin "P3.6_GPIO/PWM") (pinfunction "P3.6_GPIO/PWM_P3.6_GPIO/PWM") (pintype "bidirectional"))
      (node (ref "U$7") (pin "W_HP") (pinfunction "W_HP_W_HP") (pintype "bidirectional"))
    )
    (net (code "22") (name "HP_W_Y") (class "Default")
      (node (ref "MOTOR_Y") (pin "P$6") (pinfunction "P$6_P$6") (pintype "bidirectional"))
      (node (ref "R22") (pin "2") (pinfunction "2_2") (pintype "passive"))
      (node (ref "U$10") (pin "P3.6_GPIO/PWM") (pinfunction "P3.6_GPIO/PWM_P3.6_GPIO/PWM") (pintype "bidirectional"))
      (node (ref "U$12") (pin "W_HP") (pinfunction "W_HP_W_HP") (pintype "bidirectional"))
    )
    (net (code "23") (name "HP_W_Z") (class "Default")
      (node (ref "MOTOR_Z") (pin "P$6") (pinfunction "P$6_P$6") (pintype "bidirectional"))
      (node (ref "R30") (pin "2") (pinfunction "2_2") (pintype "passive"))
      (node (ref "U$13") (pin "P3.6_GPIO/PWM") (pinfunction "P3.6_GPIO/PWM_P3.6_GPIO/PWM") (pintype "bidirectional"))
      (node (ref "U$15") (pin "W_HP") (pinfunction "W_HP_W_HP") (pintype "bidirectional"))
    )
    (net (code "24") (name "M_X_RX") (class "Default")
      (node (ref "SERIAL_X") (pin "2") (pinfunction "2_2") (pintype "passive"))
      (node (ref "U$3") (pin "P2.6_GPIO/PWM") (pinfunction "P2.6_GPIO/PWM_P2.6_GPIO/PWM") (pintype "bidirectional"))
    )
    (net (code "25") (name "M_X_TX") (class "Default")
      (node (ref "SERIAL_X") (pin "1") (pinfunction "1_1") (pintype "passive"))
      (node (ref "U$3") (pin "P2.5_GPIO") (pinfunction "P2.5_GPIO_P2.5_GPIO") (pintype "bidirectional"))
    )
    (net (code "26") (name "M_Y_RX") (class "Default")
      (node (ref "SERIAL_Y") (pin "2") (pinfunction "2_2") (pintype "passive"))
      (node (ref "U$10") (pin "P2.6_GPIO/PWM") (pinfunction "P2.6_GPIO/PWM_P2.6_GPIO/PWM") (pintype "bidirectional"))
    )
    (net (code "27") (name "M_Y_TX") (class "Default")
      (node (ref "SERIAL_Y") (pin "1") (pinfunction "1_1") (pintype "passive"))
      (node (ref "U$10") (pin "P2.5_GPIO") (pinfunction "P2.5_GPIO_P2.5_GPIO") (pintype "bidirectional"))
    )
    (net (code "28") (name "M_Z_RX") (class "Default")
      (node (ref "SERIAL_Z") (pin "2") (pinfunction "2_2") (pintype "passive"))
      (node (ref "U$13") (pin "P2.6_GPIO/PWM") (pinfunction "P2.6_GPIO/PWM_P2.6_GPIO/PWM") (pintype "bidirectional"))
    )
    (net (code "29") (name "M_Z_TX") (class "Default")
      (node (ref "SERIAL_Z") (pin "1") (pinfunction "1_1") (pintype "passive"))
      (node (ref "U$13") (pin "P2.5_GPIO") (pinfunction "P2.5_GPIO_P2.5_GPIO") (pintype "bidirectional"))
    )
    (net (code "30") (name "Net-(C1-Pad1)") (class "Default")
      (node (ref "C1") (pin "1") (pinfunction "1_1") (pintype "passive"))
      (node (ref "U$7") (pin "RETRY") (pinfunction "RETRY_RETRY") (pintype "bidirectional"))
    )
    (net (code "31") (name "Net-(C2-Pad1)") (class "Default")
      (node (ref "C2") (pin "1") (pinfunction "1_1") (pintype "passive"))
      (node (ref "U$7") (pin "CPN") (pinfunction "CPN_CPN") (pintype "bidirectional"))
    )
    (net (code "32") (name "Net-(C2-Pad2)") (class "Default")
      (node (ref "C2") (pin "2") (pinfunction "2_2") (pintype "passive"))
      (node (ref "U$7") (pin "CPP") (pinfunction "CPP_CPP") (pintype "bidirectional"))
    )
    (net (code "33") (name "Net-(C3-Pad2)") (class "Default")
      (node (ref "C3") (pin "2") (pinfunction "2_2") (pintype "passive"))
      (node (ref "U$7") (pin "VCP") (pinfunction "VCP_VCP") (pintype "bidirectional"))
    )
    (net (code "34") (name "Net-(C11-Pad1)") (class "Default")
      (node (ref "C11") (pin "1") (pinfunction "1_1") (pintype "passive"))
      (node (ref "U$12") (pin "RETRY") (pinfunction "RETRY_RETRY") (pintype "bidirectional"))
    )
    (net (code "35") (name "Net-(C12-Pad1)") (class "Default")
      (node (ref "C12") (pin "1") (pinfunction "1_1") (pintype "passive"))
      (node (ref "U$12") (pin "CPN") (pinfunction "CPN_CPN") (pintype "bidirectional"))
    )
    (net (code "36") (name "Net-(C12-Pad2)") (class "Default")
      (node (ref "C12") (pin "2") (pinfunction "2_2") (pintype "passive"))
      (node (ref "U$12") (pin "CPP") (pinfunction "CPP_CPP") (pintype "bidirectional"))
    )
    (net (code "37") (name "Net-(C13-Pad2)") (class "Default")
      (node (ref "C13") (pin "2") (pinfunction "2_2") (pintype "passive"))
      (node (ref "U$12") (pin "VCP") (pinfunction "VCP_VCP") (pintype "bidirectional"))
    )
    (net (code "38") (name "Net-(C18-Pad1)") (class "Default")
      (node (ref "C18") (pin "1") (pinfunction "1_1") (pintype "passive"))
      (node (ref "U$15") (pin "RETRY") (pinfunction "RETRY_RETRY") (pintype "bidirectional"))
    )
    (net (code "39") (name "Net-(C19-Pad1)") (class "Default")
      (node (ref "C19") (pin "1") (pinfunction "1_1") (pintype "passive"))
      (node (ref "U$15") (pin "CPN") (pinfunction "CPN_CPN") (pintype "bidirectional"))
    )
    (net (code "40") (name "Net-(C19-Pad2)") (class "Default")
      (node (ref "C19") (pin "2") (pinfunction "2_2") (pintype "passive"))
      (node (ref "U$15") (pin "CPP") (pinfunction "CPP_CPP") (pintype "bidirectional"))
    )
    (net (code "41") (name "Net-(C20-Pad2)") (class "Default")
      (node (ref "C20") (pin "2") (pinfunction "2_2") (pintype "passive"))
      (node (ref "U$15") (pin "VCP") (pinfunction "VCP_VCP") (pintype "bidirectional"))
    )
    (net (code "42") (name "Net-(CMTMOD_X-SIG)") (class "Default")
      (node (ref "CMTMOD_X") (pin "P$2") (pinfunction "SIG_P$2") (pintype "bidirectional"))
      (node (ref "U$7") (pin "CMTMOD") (pinfunction "CMTMOD_CMTMOD") (pintype "bidirectional"))
    )
    (net (code "43") (name "Net-(CMTMOD_Y-SIG)") (class "Default")
      (node (ref "CMTMOD_Y") (pin "P$2") (pinfunction "SIG_P$2") (pintype "bidirectional"))
      (node (ref "U$12") (pin "CMTMOD") (pinfunction "CMTMOD_CMTMOD") (pintype "bidirectional"))
    )
    (net (code "44") (name "Net-(CMTMOD_Z-SIG)") (class "Default")
      (node (ref "CMTMOD_Z") (pin "P$2") (pinfunction "SIG_P$2") (pintype "bidirectional"))
      (node (ref "U$15") (pin "CMTMOD") (pinfunction "CMTMOD_CMTMOD") (pintype "bidirectional"))
    )
    (net (code "45") (name "Net-(D1-PadC)") (class "Default")
      (node (ref "D1") (pin "C") (pinfunction "C_C") (pintype "passive"))
      (node (ref "R9") (pin "2") (pinfunction "2_2") (pintype "passive"))
    )
    (net (code "46") (name "Net-(D3-PadC)") (class "Default")
      (node (ref "D3") (pin "C") (pinfunction "C_C") (pintype "passive"))
      (node (ref "R10") (pin "2") (pinfunction "2_2") (pintype "passive"))
    )
    (net (code "47") (name "Net-(D4-PadC)") (class "Default")
      (node (ref "D4") (pin "C") (pinfunction "C_C") (pintype "passive"))
      (node (ref "R11") (pin "2") (pinfunction "2_2") (pintype "passive"))
    )
    (net (code "48") (name "Net-(D5-+)") (class "Default")
      (node (ref "C32") (pin "2") (pinfunction "2_2") (pintype "passive"))
      (node (ref "D5") (pin "P$1") (pinfunction "+_P$1") (pintype "bidirectional"))
      (node (ref "L2") (pin "P$1") (pinfunction "1A_P$1") (pintype "bidirectional"))
    )
    (net (code "49") (name "Net-(DAA_X-SIG)") (class "Default")
      (node (ref "DAA_X") (pin "P$2") (pinfunction "SIG_P$2") (pintype "bidirectional"))
      (node (ref "U$7") (pin "DAA") (pinfunction "DAA_DAA") (pintype "bidirectional"))
    )
    (net (code "50") (name "Net-(DAA_Y-SIG)") (class "Default")
      (node (ref "DAA_Y") (pin "P$2") (pinfunction "SIG_P$2") (pintype "bidirectional"))
      (node (ref "U$12") (pin "DAA") (pinfunction "DAA_DAA") (pintype "bidirectional"))
    )
    (net (code "51") (name "Net-(DAA_Z-SIG)") (class "Default")
      (node (ref "DAA_Z") (pin "P$2") (pinfunction "SIG_P$2") (pintype "bidirectional"))
      (node (ref "U$15") (pin "DAA") (pinfunction "DAA_DAA") (pintype "bidirectional"))
    )
    (net (code "52") (name "Net-(L2-2A)") (class "Default")
      (node (ref "C32") (pin "1") (pinfunction "1_1") (pintype "passive"))
      (node (ref "L2") (pin "P$3") (pinfunction "2A_P$3") (pintype "bidirectional"))
      (node (ref "U$6") (pin "P$3") (pinfunction "SW_P$3") (pintype "bidirectional"))
      (node (ref "U$6") (pin "P$4") (pinfunction "SW_P$4") (pintype "bidirectional"))
    )
    (net (code "53") (name "Net-(MOTOR_X-PadP$1)") (class "Default")
      (node (ref "MOTOR_X") (pin "P$1") (pinfunction "P$1_P$1") (pintype "bidirectional"))
      (node (ref "U$7") (pin "W") (pinfunction "W_W") (pintype "bidirectional"))
    )
    (net (code "54") (name "Net-(MOTOR_X-PadP$2)") (class "Default")
      (node (ref "MOTOR_X") (pin "P$2") (pinfunction "P$2_P$2") (pintype "bidirectional"))
      (node (ref "U$7") (pin "V") (pinfunction "V_V") (pintype "bidirectional"))
    )
    (net (code "55") (name "Net-(MOTOR_X-PadP$3)") (class "Default")
      (node (ref "MOTOR_X") (pin "P$3") (pinfunction "P$3_P$3") (pintype "bidirectional"))
      (node (ref "U$7") (pin "U") (pinfunction "U_U") (pintype "bidirectional"))
    )
    (net (code "56") (name "Net-(MOTOR_Y-PadP$1)") (class "Default")
      (node (ref "MOTOR_Y") (pin "P$1") (pinfunction "P$1_P$1") (pintype "bidirectional"))
      (node (ref "U$12") (pin "W") (pinfunction "W_W") (pintype "bidirectional"))
    )
    (net (code "57") (name "Net-(MOTOR_Y-PadP$2)") (class "Default")
      (node (ref "MOTOR_Y") (pin "P$2") (pinfunction "P$2_P$2") (pintype "bidirectional"))
      (node (ref "U$12") (pin "V") (pinfunction "V_V") (pintype "bidirectional"))
    )
    (net (code "58") (name "Net-(MOTOR_Y-PadP$3)") (class "Default")
      (node (ref "MOTOR_Y") (pin "P$3") (pinfunction "P$3_P$3") (pintype "bidirectional"))
      (node (ref "U$12") (pin "U") (pinfunction "U_U") (pintype "bidirectional"))
    )
    (net (code "59") (name "Net-(MOTOR_Z-PadP$1)") (class "Default")
      (node (ref "MOTOR_Z") (pin "P$1") (pinfunction "P$1_P$1") (pintype "bidirectional"))
      (node (ref "U$15") (pin "W") (pinfunction "W_W") (pintype "bidirectional"))
    )
    (net (code "60") (name "Net-(MOTOR_Z-PadP$2)") (class "Default")
      (node (ref "MOTOR_Z") (pin "P$2") (pinfunction "P$2_P$2") (pintype "bidirectional"))
      (node (ref "U$15") (pin "V") (pinfunction "V_V") (pintype "bidirectional"))
    )
    (net (code "61") (name "Net-(MOTOR_Z-PadP$3)") (class "Default")
      (node (ref "MOTOR_Z") (pin "P$3") (pinfunction "P$3_P$3") (pintype "bidirectional"))
      (node (ref "U$15") (pin "U") (pinfunction "U_U") (pintype "bidirectional"))
    )
    (net (code "62") (name "Net-(MSP_X_DEBUG-P2.0_TXD)") (class "Default")
      (node (ref "MSP_X_DEBUG") (pin "3") (pinfunction "P2.0_TXD_3") (pintype "bidirectional"))
      (node (ref "U$3") (pin "P2.0_TXD") (pinfunction "P2.0_TXD_P2.0_TXD") (pintype "bidirectional"))
    )
    (net (code "63") (name "Net-(MSP_X_DEBUG-P2.1_RXD)") (class "Default")
      (node (ref "MSP_X_DEBUG") (pin "4") (pinfunction "P2.1_RXD_4") (pintype "bidirectional"))
      (node (ref "U$3") (pin "P2.1_RXD") (pinfunction "P2.1_RXD_P2.1_RXD") (pintype "bidirectional"))
    )
    (net (code "64") (name "Net-(MSP_X_DEBUG-P3.4_GPIO_DEBUG)") (class "Default")
      (node (ref "MSP_X_DEBUG") (pin "7") (pinfunction "P3.4_GPIO_DEBUG_7") (pintype "bidirectional"))
      (node (ref "U$3") (pin "P3.4_GPIO_DEBUG") (pinfunction "P3.4_GPIO_DEBUG_P3.4_GPIO_DEBUG") (pintype "bidirectional"))
    )
    (net (code "65") (name "Net-(MSP_X_DEBUG-P3.5_GPIO_DEBUG)") (class "Default")
      (node (ref "D1") (pin "A") (pinfunction "A_A") (pintype "passive"))
      (node (ref "MSP_X_DEBUG") (pin "8") (pinfunction "P3.5_GPIO_DEBUG_8") (pintype "bidirectional"))
      (node (ref "U$3") (pin "P3.5_GPIO_DEBUG") (pinfunction "P3.5_GPIO_DEBUG_P3.5_GPIO_DEBUG") (pintype "bidirectional"))
    )
    (net (code "66") (name "Net-(MSP_X_DEBUG-PadSBWTCK)") (class "Default")
      (node (ref "MSP_X_DEBUG") (pin "SBWTCK") (pinfunction "SBWTCK_SBWTCK") (pintype "bidirectional"))
      (node (ref "U$3") (pin "SBWTCK") (pinfunction "SBWTCK_SBWTCK") (pintype "bidirectional"))
    )
    (net (code "67") (name "Net-(MSP_X_DEBUG-SBWTDIO)") (class "Default")
      (node (ref "MSP_X_DEBUG") (pin "2") (pinfunction "SBWTDIO_2") (pintype "bidirectional"))
      (node (ref "U$3") (pin "SBWTDIO") (pinfunction "SBWTDIO_SBWTDIO") (pintype "bidirectional"))
    )
    (net (code "68") (name "Net-(MSP_Y_DEBUG-P2.0_TXD)") (class "Default")
      (node (ref "MSP_Y_DEBUG") (pin "3") (pinfunction "P2.0_TXD_3") (pintype "bidirectional"))
      (node (ref "U$10") (pin "P2.0_TXD") (pinfunction "P2.0_TXD_P2.0_TXD") (pintype "bidirectional"))
    )
    (net (code "69") (name "Net-(MSP_Y_DEBUG-P2.1_RXD)") (class "Default")
      (node (ref "MSP_Y_DEBUG") (pin "4") (pinfunction "P2.1_RXD_4") (pintype "bidirectional"))
      (node (ref "U$10") (pin "P2.1_RXD") (pinfunction "P2.1_RXD_P2.1_RXD") (pintype "bidirectional"))
    )
    (net (code "70") (name "Net-(MSP_Y_DEBUG-P3.4_GPIO_DEBUG)") (class "Default")
      (node (ref "MSP_Y_DEBUG") (pin "7") (pinfunction "P3.4_GPIO_DEBUG_7") (pintype "bidirectional"))
      (node (ref "U$10") (pin "P3.4_GPIO_DEBUG") (pinfunction "P3.4_GPIO_DEBUG_P3.4_GPIO_DEBUG") (pintype "bidirectional"))
    )
    (net (code "71") (name "Net-(MSP_Y_DEBUG-P3.5_GPIO_DEBUG)") (class "Default")
      (node (ref "D3") (pin "A") (pinfunction "A_A") (pintype "passive"))
      (node (ref "MSP_Y_DEBUG") (pin "8") (pinfunction "P3.5_GPIO_DEBUG_8") (pintype "bidirectional"))
      (node (ref "U$10") (pin "P3.5_GPIO_DEBUG") (pinfunction "P3.5_GPIO_DEBUG_P3.5_GPIO_DEBUG") (pintype "bidirectional"))
    )
    (net (code "72") (name "Net-(MSP_Y_DEBUG-PadSBWTCK)") (class "Default")
      (node (ref "MSP_Y_DEBUG") (pin "SBWTCK") (pinfunction "SBWTCK_SBWTCK") (pintype "bidirectional"))
      (node (ref "U$10") (pin "SBWTCK") (pinfunction "SBWTCK_SBWTCK") (pintype "bidirectional"))
    )
    (net (code "73") (name "Net-(MSP_Y_DEBUG-SBWTDIO)") (class "Default")
      (node (ref "MSP_Y_DEBUG") (pin "2") (pinfunction "SBWTDIO_2") (pintype "bidirectional"))
      (node (ref "U$10") (pin "SBWTDIO") (pinfunction "SBWTDIO_SBWTDIO") (pintype "bidirectional"))
    )
    (net (code "74") (name "Net-(MSP_Z_DEBUG-P2.0_TXD)") (class "Default")
      (node (ref "MSP_Z_DEBUG") (pin "3") (pinfunction "P2.0_TXD_3") (pintype "bidirectional"))
      (node (ref "U$13") (pin "P2.0_TXD") (pinfunction "P2.0_TXD_P2.0_TXD") (pintype "bidirectional"))
    )
    (net (code "75") (name "Net-(MSP_Z_DEBUG-P2.1_RXD)") (class "Default")
      (node (ref "MSP_Z_DEBUG") (pin "4") (pinfunction "P2.1_RXD_4") (pintype "bidirectional"))
      (node (ref "U$13") (pin "P2.1_RXD") (pinfunction "P2.1_RXD_P2.1_RXD") (pintype "bidirectional"))
    )
    (net (code "76") (name "Net-(MSP_Z_DEBUG-P3.4_GPIO_DEBUG)") (class "Default")
      (node (ref "MSP_Z_DEBUG") (pin "7") (pinfunction "P3.4_GPIO_DEBUG_7") (pintype "bidirectional"))
      (node (ref "U$13") (pin "P3.4_GPIO_DEBUG") (pinfunction "P3.4_GPIO_DEBUG_P3.4_GPIO_DEBUG") (pintype "bidirectional"))
    )
    (net (code "77") (name "Net-(MSP_Z_DEBUG-P3.5_GPIO_DEBUG)") (class "Default")
      (node (ref "D4") (pin "A") (pinfunction "A_A") (pintype "passive"))
      (node (ref "MSP_Z_DEBUG") (pin "8") (pinfunction "P3.5_GPIO_DEBUG_8") (pintype "bidirectional"))
      (node (ref "U$13") (pin "P3.5_GPIO_DEBUG") (pinfunction "P3.5_GPIO_DEBUG_P3.5_GPIO_DEBUG") (pintype "bidirectional"))
    )
    (net (code "78") (name "Net-(MSP_Z_DEBUG-PadSBWTCK)") (class "Default")
      (node (ref "MSP_Z_DEBUG") (pin "SBWTCK") (pinfunction "SBWTCK_SBWTCK") (pintype "bidirectional"))
      (node (ref "U$13") (pin "SBWTCK") (pinfunction "SBWTCK_SBWTCK") (pintype "bidirectional"))
    )
    (net (code "79") (name "Net-(MSP_Z_DEBUG-SBWTDIO)") (class "Default")
      (node (ref "MSP_Z_DEBUG") (pin "2") (pinfunction "SBWTDIO_2") (pintype "bidirectional"))
      (node (ref "U$13") (pin "SBWTDIO") (pinfunction "SBWTDIO_SBWTDIO") (pintype "bidirectional"))
    )
    (net (code "80") (name "Net-(R2-Pad2)") (class "Default")
      (node (ref "R2") (pin "2") (pinfunction "2_2") (pintype "passive"))
      (node (ref "R3") (pin "1") (pinfunction "1_1") (pintype "passive"))
      (node (ref "U$7") (pin "U_HN") (pinfunction "U_HN_U_HN") (pintype "bidirectional"))
      (node (ref "U$7") (pin "V_HN") (pinfunction "V_HN_V_HN") (pintype "bidirectional"))
      (node (ref "U$7") (pin "W_HN") (pinfunction "W_HN_W_HN") (pintype "bidirectional"))
    )
    (net (code "81") (name "Net-(R7-Pad2)") (class "Default")
      (node (ref "R7") (pin "2") (pinfunction "2_2") (pintype "passive"))
      (node (ref "U$7") (pin "CS") (pinfunction "CS_CS") (pintype "bidirectional"))
    )
    (net (code "82") (name "Net-(R18-Pad2)") (class "Default")
      (node (ref "R18") (pin "2") (pinfunction "2_2") (pintype "passive"))
      (node (ref "R19") (pin "1") (pinfunction "1_1") (pintype "passive"))
      (node (ref "U$12") (pin "U_HN") (pinfunction "U_HN_U_HN") (pintype "bidirectional"))
      (node (ref "U$12") (pin "V_HN") (pinfunction "V_HN_V_HN") (pintype "bidirectional"))
      (node (ref "U$12") (pin "W_HN") (pinfunction "W_HN_W_HN") (pintype "bidirectional"))
    )
    (net (code "83") (name "Net-(R23-Pad2)") (class "Default")
      (node (ref "R23") (pin "2") (pinfunction "2_2") (pintype "passive"))
      (node (ref "U$12") (pin "CS") (pinfunction "CS_CS") (pintype "bidirectional"))
    )
    (net (code "84") (name "Net-(R26-Pad2)") (class "Default")
      (node (ref "R26") (pin "2") (pinfunction "2_2") (pintype "passive"))
      (node (ref "R27") (pin "1") (pinfunction "1_1") (pintype "passive"))
      (node (ref "U$15") (pin "U_HN") (pinfunction "U_HN_U_HN") (pintype "bidirectional"))
      (node (ref "U$15") (pin "V_HN") (pinfunction "V_HN_V_HN") (pintype "bidirectional"))
      (node (ref "U$15") (pin "W_HN") (pinfunction "W_HN_W_HN") (pintype "bidirectional"))
    )
    (net (code "85") (name "Net-(R31-Pad2)") (class "Default")
      (node (ref "R31") (pin "2") (pinfunction "2_2") (pintype "passive"))
      (node (ref "U$15") (pin "CS") (pinfunction "CS_CS") (pintype "bidirectional"))
    )
    (net (code "86") (name "Net-(U$6-EN{slash}UVLO)") (class "Default")
      (node (ref "R15") (pin "2") (pinfunction "2_2") (pintype "passive"))
      (node (ref "U$6") (pin "P$8") (pinfunction "EN/UVLO_P$8") (pintype "bidirectional"))
    )
    (net (code "87") (name "Net-(U$6-FBX)") (class "Default")
      (node (ref "C34") (pin "2") (pinfunction "2_2") (pintype "passive"))
      (node (ref "R16") (pin "1") (pinfunction "1_1") (pintype "passive"))
      (node (ref "R33") (pin "2") (pinfunction "2_2") (pintype "passive"))
      (node (ref "U$6") (pin "P$1") (pinfunction "FBX_P$1") (pintype "bidirectional"))
    )
    (net (code "88") (name "Net-(U$6-INT_VCC)") (class "Default")
      (node (ref "C27") (pin "1") (pinfunction "1_1") (pintype "passive"))
      (node (ref "U$6") (pin "P$7") (pinfunction "INT_VCC_P$7") (pintype "bidirectional"))
    )
    (net (code "89") (name "Net-(U2-BYP)") (class "Default")
      (node (ref "C16") (pin "2") (pinfunction "2_2") (pintype "passive"))
      (node (ref "U2") (pin "P$4") (pinfunction "BYP_P$4") (pintype "bidirectional"))
    )
    (net (code "90") (name "Net-(U3-BYP)") (class "Default")
      (node (ref "C29") (pin "2") (pinfunction "2_2") (pintype "passive"))
      (node (ref "U3") (pin "P$4") (pinfunction "BYP_P$4") (pintype "bidirectional"))
    )
    (net (code "91") (name "PWM_X") (class "Default")
      (node (ref "MOTOR_X_DEBUG") (pin "3") (pinfunction "3_3") (pintype "passive"))
      (node (ref "U$3") (pin "P1.7_GPIO/PWM") (pinfunction "P1.7_GPIO/PWM_P1.7_GPIO/PWM") (pintype "bidirectional"))
      (node (ref "U$7") (pin "PWM") (pinfunction "PWM_PWM") (pintype "bidirectional"))
    )
    (net (code "92") (name "PWM_Y") (class "Default")
      (node (ref "MOTOR_Y_DEBUG") (pin "3") (pinfunction "3_3") (pintype "passive"))
      (node (ref "U$10") (pin "P1.7_GPIO/PWM") (pinfunction "P1.7_GPIO/PWM_P1.7_GPIO/PWM") (pintype "bidirectional"))
      (node (ref "U$12") (pin "PWM") (pinfunction "PWM_PWM") (pintype "bidirectional"))
    )
    (net (code "93") (name "PWM_Z") (class "Default")
      (node (ref "MOTOR_Z_DEBUG") (pin "3") (pinfunction "3_3") (pintype "passive"))
      (node (ref "U$13") (pin "P1.7_GPIO/PWM") (pinfunction "P1.7_GPIO/PWM_P1.7_GPIO/PWM") (pintype "bidirectional"))
      (node (ref "U$15") (pin "PWM") (pinfunction "PWM_PWM") (pintype "bidirectional"))
    )
    (net (code "94") (name "RD_X") (class "Default")
      (node (ref "R1") (pin "1") (pinfunction "1_1") (pintype "passive"))
      (node (ref "U$3") (pin "P4.0_GPIO") (pinfunction "P4.0_GPIO_P4.0_GPIO") (pintype "bidirectional"))
      (node (ref "U$7") (pin "RD") (pinfunction "RD_RD") (pintype "bidirectional"))
    )
    (net (code "95") (name "RD_Y") (class "Default")
      (node (ref "R17") (pin "1") (pinfunction "1_1") (pintype "passive"))
      (node (ref "U$10") (pin "P4.0_GPIO") (pinfunction "P4.0_GPIO_P4.0_GPIO") (pintype "bidirectional"))
      (node (ref "U$12") (pin "RD") (pinfunction "RD_RD") (pintype "bidirectional"))
    )
    (net (code "96") (name "RD_Z") (class "Default")
      (node (ref "R25") (pin "1") (pinfunction "1_1") (pintype "passive"))
      (node (ref "U$13") (pin "P4.0_GPIO") (pinfunction "P4.0_GPIO_P4.0_GPIO") (pintype "bidirectional"))
      (node (ref "U$15") (pin "RD") (pinfunction "RD_RD") (pintype "bidirectional"))
    )
    (net (code "97") (name "SYNC1") (class "Default")
      (node (ref "PC104") (pin "P$45") (pinfunction "SYNC1_P$45") (pintype "bidirectional"))
      (node (ref "U$10") (pin "P7.2_SYNC1") (pinfunction "P7.2_SYNC1_P7.2_SYNC1") (pintype "bidirectional"))
      (node (ref "U$13") (pin "P7.2_SYNC1") (pinfunction "P7.2_SYNC1_P7.2_SYNC1") (pintype "bidirectional"))
      (node (ref "U$3") (pin "P7.2_SYNC1") (pinfunction "P7.2_SYNC1_P7.2_SYNC1") (pintype "bidirectional"))
    )
    (net (code "98") (name "SYNC2") (class "Default")
      (node (ref "PC104") (pin "P$49") (pinfunction "SYNC2_P$49") (pintype "bidirectional"))
      (node (ref "U$10") (pin "PJ.3_SYNC2") (pinfunction "PJ.3_SYNC2_PJ.3_SYNC2") (pintype "bidirectional"))
      (node (ref "U$13") (pin "PJ.3_SYNC2") (pinfunction "PJ.3_SYNC2_PJ.3_SYNC2") (pintype "bidirectional"))
      (node (ref "U$3") (pin "PJ.3_SYNC2") (pinfunction "PJ.3_SYNC2_PJ.3_SYNC2") (pintype "bidirectional"))
    )
    (net (code "99") (name "VBAT") (class "Default")
      (node (ref "C17") (pin "2") (pinfunction "2_2") (pintype "passive"))
      (node (ref "C26") (pin "1") (pinfunction "1_1") (pintype "passive"))
      (node (ref "C30") (pin "2") (pinfunction "2_2") (pintype "passive"))
      (node (ref "C8") (pin "1") (pinfunction "1_1") (pintype "passive"))
      (node (ref "L2") (pin "P$4") (pinfunction "2B_P$4") (pintype "bidirectional"))
      (node (ref "PC104") (pin "P$69") (pinfunction "WHEEL_VBAT_P$69") (pintype "bidirectional"))
      (node (ref "PC104") (pin "P$70") (pinfunction "WHEEL_VBAT_P$70") (pintype "bidirectional"))
      (node (ref "R15") (pin "1") (pinfunction "1_1") (pintype "passive"))
      (node (ref "U$6") (pin "P$6") (pinfunction "V_IN_P$6") (pintype "bidirectional"))
      (node (ref "U2") (pin "P$1") (pinfunction "IN_P$1") (pintype "bidirectional"))
      (node (ref "U2") (pin "P$3") (pinfunction "EN_P$3") (pintype "bidirectional"))
      (node (ref "U3") (pin "P$1") (pinfunction "IN_P$1") (pintype "bidirectional"))
      (node (ref "U3") (pin "P$3") (pinfunction "EN_P$3") (pintype "bidirectional"))
    )
    (net (code "100") (name "VINT_X") (class "Default")
      (node (ref "C4") (pin "2") (pinfunction "2_2") (pintype "passive"))
      (node (ref "CMTMOD_X") (pin "P$3") (pinfunction "VCC_P$3") (pintype "bidirectional"))
      (node (ref "DAA_X") (pin "P$3") (pinfunction "VCC_P$3") (pintype "bidirectional"))
      (node (ref "MOTOR_X") (pin "P$5") (pinfunction "P$5_P$5") (pintype "bidirectional"))
      (node (ref "R1") (pin "2") (pinfunction "2_2") (pintype "passive"))
      (node (ref "R3") (pin "2") (pinfunction "2_2") (pintype "passive"))
      (node (ref "R4") (pin "1") (pinfunction "1_1") (pintype "passive"))
      (node (ref "R5") (pin "1") (pinfunction "1_1") (pintype "passive"))
      (node (ref "R6") (pin "1") (pinfunction "1_1") (pintype "passive"))
      (node (ref "R8") (pin "1") (pinfunction "1_1") (pintype "passive"))
      (node (ref "U$7") (pin "VINT") (pinfunction "VINT_VINT") (pintype "bidirectional"))
    )
    (net (code "101") (name "VINT_Y") (class "Default")
      (node (ref "C14") (pin "2") (pinfunction "2_2") (pintype "passive"))
      (node (ref "CMTMOD_Y") (pin "P$3") (pinfunction "VCC_P$3") (pintype "bidirectional"))
      (node (ref "DAA_Y") (pin "P$3") (pinfunction "VCC_P$3") (pintype "bidirectional"))
      (node (ref "MOTOR_Y") (pin "P$5") (pinfunction "P$5_P$5") (pintype "bidirectional"))
      (node (ref "R17") (pin "2") (pinfunction "2_2") (pintype "passive"))
      (node (ref "R19") (pin "2") (pinfunction "2_2") (pintype "passive"))
      (node (ref "R20") (pin "1") (pinfunction "1_1") (pintype "passive"))
      (node (ref "R21") (pin "1") (pinfunction "1_1") (pintype "passive"))
      (node (ref "R22") (pin "1") (pinfunction "1_1") (pintype "passive"))
      (node (ref "R24") (pin "1") (pinfunction "1_1") (pintype "passive"))
      (node (ref "U$12") (pin "VINT") (pinfunction "VINT_VINT") (pintype "bidirectional"))
    )
    (net (code "102") (name "VINT_Z") (class "Default")
      (node (ref "C21") (pin "2") (pinfunction "2_2") (pintype "passive"))
      (node (ref "CMTMOD_Z") (pin "P$3") (pinfunction "VCC_P$3") (pintype "bidirectional"))
      (node (ref "DAA_Z") (pin "P$3") (pinfunction "VCC_P$3") (pintype "bidirectional"))
      (node (ref "MOTOR_Z") (pin "P$5") (pinfunction "P$5_P$5") (pintype "bidirectional"))
      (node (ref "R25") (pin "2") (pinfunction "2_2") (pintype "passive"))
      (node (ref "R27") (pin "2") (pinfunction "2_2") (pintype "passive"))
      (node (ref "R28") (pin "1") (pinfunction "1_1") (pintype "passive"))
      (node (ref "R29") (pin "1") (pinfunction "1_1") (pintype "passive"))
      (node (ref "R30") (pin "1") (pinfunction "1_1") (pintype "passive"))
      (node (ref "R32") (pin "1") (pinfunction "1_1") (pintype "passive"))
      (node (ref "U$15") (pin "VINT") (pinfunction "VINT_VINT") (pintype "bidirectional"))
    )
    (net (code "103") (name "VM") (class "Default")
      (node (ref "C15") (pin "2") (pinfunction "2_2") (pintype "passive"))
      (node (ref "C22") (pin "2") (pinfunction "2_2") (pintype "passive"))
      (node (ref "C33") (pin "1") (pinfunction "1_1") (pintype "passive"))
      (node (ref "C34") (pin "1") (pinfunction "1_1") (pintype "passive"))
      (node (ref "C35") (pin "1") (pinfunction "1_1") (pintype "passive"))
      (node (ref "C36") (pin "1") (pinfunction "1_1") (pintype "passive"))
      (node (ref "C5") (pin "2") (pinfunction "2_2") (pintype "passive"))
      (node (ref "D5") (pin "P$2") (pinfunction "-_P$2") (pintype "bidirectional"))
      (node (ref "R16") (pin "2") (pinfunction "2_2") (pintype "passive"))
      (node (ref "U$12") (pin "VM") (pinfunction "VM_VM") (pintype "bidirectional"))
      (node (ref "U$15") (pin "VM") (pinfunction "VM_VM") (pintype "bidirectional"))
      (node (ref "U$7") (pin "VM") (pinfunction "VM_VM") (pintype "bidirectional"))
    )
    (net (code "104") (name "unconnected-(PC104-BATT_VBAT$33-PadP$33)") (class "Default")
      (node (ref "PC104") (pin "P$33") (pinfunction "BATT_VBAT$33_P$33") (pintype "bidirectional"))
    )
    (net (code "105") (name "unconnected-(PC104-BATT_VBATT$34-PadP$34)") (class "Default")
      (node (ref "PC104") (pin "P$34") (pinfunction "BATT_VBATT$34_P$34") (pintype "bidirectional"))
    )
    (net (code "106") (name "unconnected-(PC104-BDOT_GND-PadP$87)") (class "Default")
      (node (ref "PC104") (pin "P$87") (pinfunction "BDOT_GND_P$87") (pintype "bidirectional"))
    )
    (net (code "107") (name "unconnected-(PC104-BDOT_GND-PadP$88)") (class "Default")
      (node (ref "PC104") (pin "P$88") (pinfunction "BDOT_GND_P$88") (pintype "bidirectional"))
    )
    (net (code "108") (name "unconnected-(PC104-BDOT_VBAT-PadP$85)") (class "Default")
      (node (ref "PC104") (pin "P$85") (pinfunction "BDOT_VBAT_P$85") (pintype "bidirectional"))
    )
    (net (code "109") (name "unconnected-(PC104-BDOT_VBAT-PadP$86)") (class "Default")
      (node (ref "PC104") (pin "P$86") (pinfunction "BDOT_VBAT_P$86") (pintype "bidirectional"))
    )
    (net (code "110") (name "unconnected-(PC104-COM1_GND-PadP$102)") (class "Default")
      (node (ref "PC104") (pin "P$102") (pinfunction "COM1_GND_P$102") (pintype "bidirectional"))
    )
    (net (code "111") (name "unconnected-(PC104-COM1_GND-PadP$104)") (class "Default")
      (node (ref "PC104") (pin "P$104") (pinfunction "COM1_GND_P$104") (pintype "bidirectional"))
    )
    (net (code "112") (name "unconnected-(PC104-COM1_VBAT-PadP$101)") (class "Default")
      (node (ref "PC104") (pin "P$101") (pinfunction "COM1_VBAT_P$101") (pintype "bidirectional"))
    )
    (net (code "113") (name "unconnected-(PC104-COM1_VBAT-PadP$103)") (class "Default")
      (node (ref "PC104") (pin "P$103") (pinfunction "COM1_VBAT_P$103") (pintype "bidirectional"))
    )
    (net (code "114") (name "unconnected-(PC104-COM2_GND-PadP$98)") (class "Default")
      (node (ref "PC104") (pin "P$98") (pinfunction "COM2_GND_P$98") (pintype "bidirectional"))
    )
    (net (code "115") (name "unconnected-(PC104-COM2_GND-PadP$100)") (class "Default")
      (node (ref "PC104") (pin "P$100") (pinfunction "COM2_GND_P$100") (pintype "bidirectional"))
    )
    (net (code "116") (name "unconnected-(PC104-COM2_VBAT-PadP$97)") (class "Default")
      (node (ref "PC104") (pin "P$97") (pinfunction "COM2_VBAT_P$97") (pintype "bidirectional"))
    )
    (net (code "117") (name "unconnected-(PC104-COM2_VBAT-PadP$99)") (class "Default")
      (node (ref "PC104") (pin "P$99") (pinfunction "COM2_VBAT_P$99") (pintype "bidirectional"))
    )
    (net (code "118") (name "unconnected-(PC104-DISTRI_GND-PadP$17)") (class "Default")
      (node (ref "PC104") (pin "P$17") (pinfunction "DISTRI_GND_P$17") (pintype "bidirectional"))
    )
    (net (code "119") (name "unconnected-(PC104-DISTRI_GND-PadP$19)") (class "Default")
      (node (ref "PC104") (pin "P$19") (pinfunction "DISTRI_GND_P$19") (pintype "bidirectional"))
    )
    (net (code "120") (name "unconnected-(PC104-DISTRI_GND-PadP$22)") (class "Default")
      (node (ref "PC104") (pin "P$22") (pinfunction "DISTRI_GND_P$22") (pintype "bidirectional"))
    )
    (net (code "121") (name "unconnected-(PC104-DISTRI_GND-PadP$24)") (class "Default")
      (node (ref "PC104") (pin "P$24") (pinfunction "DISTRI_GND_P$24") (pintype "bidirectional"))
    )
    (net (code "122") (name "unconnected-(PC104-DISTRI_GND-PadP$25)") (class "Default")
      (node (ref "PC104") (pin "P$25") (pinfunction "DISTRI_GND_P$25") (pintype "bidirectional"))
    )
    (net (code "123") (name "unconnected-(PC104-DISTRI_GND-PadP$27)") (class "Default")
      (node (ref "PC104") (pin "P$27") (pinfunction "DISTRI_GND_P$27") (pintype "bidirectional"))
    )
    (net (code "124") (name "unconnected-(PC104-DISTRI_GND-PadP$30)") (class "Default")
      (node (ref "PC104") (pin "P$30") (pinfunction "DISTRI_GND_P$30") (pintype "bidirectional"))
    )
    (net (code "125") (name "unconnected-(PC104-DISTRI_GND-PadP$32)") (class "Default")
      (node (ref "PC104") (pin "P$32") (pinfunction "DISTRI_GND_P$32") (pintype "bidirectional"))
    )
    (net (code "126") (name "unconnected-(PC104-DISTRI_VBAT-PadP$18)") (class "Default")
      (node (ref "PC104") (pin "P$18") (pinfunction "DISTRI_VBAT_P$18") (pintype "bidirectional"))
    )
    (net (code "127") (name "unconnected-(PC104-DISTRI_VBAT-PadP$20)") (class "Default")
      (node (ref "PC104") (pin "P$20") (pinfunction "DISTRI_VBAT_P$20") (pintype "bidirectional"))
    )
    (net (code "128") (name "unconnected-(PC104-DISTRI_VBAT-PadP$21)") (class "Default")
      (node (ref "PC104") (pin "P$21") (pinfunction "DISTRI_VBAT_P$21") (pintype "bidirectional"))
    )
    (net (code "129") (name "unconnected-(PC104-DISTRI_VBAT-PadP$23)") (class "Default")
      (node (ref "PC104") (pin "P$23") (pinfunction "DISTRI_VBAT_P$23") (pintype "bidirectional"))
    )
    (net (code "130") (name "unconnected-(PC104-DISTRI_VBAT-PadP$26)") (class "Default")
      (node (ref "PC104") (pin "P$26") (pinfunction "DISTRI_VBAT_P$26") (pintype "bidirectional"))
    )
    (net (code "131") (name "unconnected-(PC104-DISTRI_VBAT-PadP$28)") (class "Default")
      (node (ref "PC104") (pin "P$28") (pinfunction "DISTRI_VBAT_P$28") (pintype "bidirectional"))
    )
    (net (code "132") (name "unconnected-(PC104-DISTRI_VBAT-PadP$29)") (class "Default")
      (node (ref "PC104") (pin "P$29") (pinfunction "DISTRI_VBAT_P$29") (pintype "bidirectional"))
    )
    (net (code "133") (name "unconnected-(PC104-DISTRI_VBAT-PadP$31)") (class "Default")
      (node (ref "PC104") (pin "P$31") (pinfunction "DISTRI_VBAT_P$31") (pintype "bidirectional"))
    )
    (net (code "134") (name "unconnected-(PC104-ESTIMAT_GND-PadP$79)") (class "Default")
      (node (ref "PC104") (pin "P$79") (pinfunction "ESTIMAT_GND_P$79") (pintype "bidirectional"))
    )
    (net (code "135") (name "unconnected-(PC104-ESTIMAT_GND-PadP$80)") (class "Default")
      (node (ref "PC104") (pin "P$80") (pinfunction "ESTIMAT_GND_P$80") (pintype "bidirectional"))
    )
    (net (code "136") (name "unconnected-(PC104-ESTIMAT_VBAT-PadP$77)") (class "Default")
      (node (ref "PC104") (pin "P$77") (pinfunction "ESTIMAT_VBAT_P$77") (pintype "bidirectional"))
    )
    (net (code "137") (name "unconnected-(PC104-ESTIMAT_VBAT-PadP$78)") (class "Default")
      (node (ref "PC104") (pin "P$78") (pinfunction "ESTIMAT_VBAT_P$78") (pintype "bidirectional"))
    )
    (net (code "138") (name "unconnected-(PC104-GEN_VBATT$35-PadP$35)") (class "Default")
      (node (ref "PC104") (pin "P$35") (pinfunction "GEN_VBATT$35_P$35") (pintype "bidirectional"))
    )
    (net (code "139") (name "unconnected-(PC104-GEN_VBATT$36-PadP$36)") (class "Default")
      (node (ref "PC104") (pin "P$36") (pinfunction "GEN_VBATT$36_P$36") (pintype "bidirectional"))
    )
    (net (code "140") (name "unconnected-(PC104-P-PadP$59)") (class "Default")
      (node (ref "PC104") (pin "P$59") (pinfunction "P_P$59") (pintype "bidirectional"))
    )
    (net (code "141") (name "unconnected-(PC104-PPT_GND-PadP$1)") (class "Default")
      (node (ref "PC104") (pin "P$1") (pinfunction "PPT_GND_P$1") (pintype "bidirectional"))
    )
    (net (code "142") (name "unconnected-(PC104-PPT_GND-PadP$3)") (class "Default")
      (node (ref "PC104") (pin "P$3") (pinfunction "PPT_GND_P$3") (pintype "bidirectional"))
    )
    (net (code "143") (name "unconnected-(PC104-PPT_GND-PadP$6)") (class "Default")
      (node (ref "PC104") (pin "P$6") (pinfunction "PPT_GND_P$6") (pintype "bidirectional"))
    )
    (net (code "144") (name "unconnected-(PC104-PPT_GND-PadP$8)") (class "Default")
      (node (ref "PC104") (pin "P$8") (pinfunction "PPT_GND_P$8") (pintype "bidirectional"))
    )
    (net (code "145") (name "unconnected-(PC104-PPT_GND-PadP$9)") (class "Default")
      (node (ref "PC104") (pin "P$9") (pinfunction "PPT_GND_P$9") (pintype "bidirectional"))
    )
    (net (code "146") (name "unconnected-(PC104-PPT_GND-PadP$11)") (class "Default")
      (node (ref "PC104") (pin "P$11") (pinfunction "PPT_GND_P$11") (pintype "bidirectional"))
    )
    (net (code "147") (name "unconnected-(PC104-PPT_GND-PadP$14)") (class "Default")
      (node (ref "PC104") (pin "P$14") (pinfunction "PPT_GND_P$14") (pintype "bidirectional"))
    )
    (net (code "148") (name "unconnected-(PC104-PPT_GND-PadP$16)") (class "Default")
      (node (ref "PC104") (pin "P$16") (pinfunction "PPT_GND_P$16") (pintype "bidirectional"))
    )
    (net (code "149") (name "unconnected-(PC104-PPT_VBAT-PadP$2)") (class "Default")
      (node (ref "PC104") (pin "P$2") (pinfunction "PPT_VBAT_P$2") (pintype "bidirectional"))
    )
    (net (code "150") (name "unconnected-(PC104-PPT_VBAT-PadP$4)") (class "Default")
      (node (ref "PC104") (pin "P$4") (pinfunction "PPT_VBAT_P$4") (pintype "bidirectional"))
    )
    (net (code "151") (name "unconnected-(PC104-PPT_VBAT-PadP$5)") (class "Default")
      (node (ref "PC104") (pin "P$5") (pinfunction "PPT_VBAT_P$5") (pintype "bidirectional"))
    )
    (net (code "152") (name "unconnected-(PC104-PPT_VBAT-PadP$7)") (class "Default")
      (node (ref "PC104") (pin "P$7") (pinfunction "PPT_VBAT_P$7") (pintype "bidirectional"))
    )
    (net (code "153") (name "unconnected-(PC104-PPT_VBAT-PadP$10)") (class "Default")
      (node (ref "PC104") (pin "P$10") (pinfunction "PPT_VBAT_P$10") (pintype "bidirectional"))
    )
    (net (code "154") (name "unconnected-(PC104-PPT_VBAT-PadP$12)") (class "Default")
      (node (ref "PC104") (pin "P$12") (pinfunction "PPT_VBAT_P$12") (pintype "bidirectional"))
    )
    (net (code "155") (name "unconnected-(PC104-PPT_VBAT-PadP$13)") (class "Default")
      (node (ref "PC104") (pin "P$13") (pinfunction "PPT_VBAT_P$13") (pintype "bidirectional"))
    )
    (net (code "156") (name "unconnected-(PC104-PPT_VBAT-PadP$15)") (class "Default")
      (node (ref "PC104") (pin "P$15") (pinfunction "PPT_VBAT_P$15") (pintype "bidirectional"))
    )
    (net (code "157") (name "unconnected-(PC104-PadP$37)") (class "Default")
      (node (ref "PC104") (pin "P$37") (pinfunction "P$37_P$37") (pintype "bidirectional"))
    )
    (net (code "158") (name "unconnected-(PC104-PadP$38)") (class "Default")
      (node (ref "PC104") (pin "P$38") (pinfunction "P$38_P$38") (pintype "bidirectional"))
    )
    (net (code "159") (name "unconnected-(PC104-PadP$39)") (class "Default")
      (node (ref "PC104") (pin "P$39") (pinfunction "P$39_P$39") (pintype "bidirectional"))
    )
    (net (code "160") (name "unconnected-(PC104-PadP$40)") (class "Default")
      (node (ref "PC104") (pin "P$40") (pinfunction "P$40_P$40") (pintype "bidirectional"))
    )
    (net (code "161") (name "unconnected-(PC104-PadP$41)") (class "Default")
      (node (ref "PC104") (pin "P$41") (pinfunction "P$41_P$41") (pintype "bidirectional"))
    )
    (net (code "162") (name "unconnected-(PC104-PadP$42)") (class "Default")
      (node (ref "PC104") (pin "P$42") (pinfunction "P$42_P$42") (pintype "bidirectional"))
    )
    (net (code "163") (name "unconnected-(PC104-PadP$43)") (class "Default")
      (node (ref "PC104") (pin "P$43") (pinfunction "P$43_P$43") (pintype "bidirectional"))
    )
    (net (code "164") (name "unconnected-(PC104-PadP$44)") (class "Default")
      (node (ref "PC104") (pin "P$44") (pinfunction "P$44_P$44") (pintype "bidirectional"))
    )
    (net (code "165") (name "unconnected-(PC104-PadP$46)") (class "Default")
      (node (ref "PC104") (pin "P$46") (pinfunction "P$46_P$46") (pintype "bidirectional"))
    )
    (net (code "166") (name "unconnected-(PC104-PadP$47)") (class "Default")
      (node (ref "PC104") (pin "P$47") (pinfunction "P$47_P$47") (pintype "bidirectional"))
    )
    (net (code "167") (name "unconnected-(PC104-PadP$48)") (class "Default")
      (node (ref "PC104") (pin "P$48") (pinfunction "P$48_P$48") (pintype "bidirectional"))
    )
    (net (code "168") (name "unconnected-(PC104-PadP$50)") (class "Default")
      (node (ref "PC104") (pin "P$50") (pinfunction "P$50_P$50") (pintype "bidirectional"))
    )
    (net (code "169") (name "unconnected-(PC104-PadP$54)") (class "Default")
      (node (ref "PC104") (pin "P$54") (pinfunction "P$54_P$54") (pintype "bidirectional"))
    )
    (net (code "170") (name "unconnected-(PC104-PadP$58)") (class "Default")
      (node (ref "PC104") (pin "P$58") (pinfunction "P$58_P$58") (pintype "bidirectional"))
    )
    (net (code "171") (name "unconnected-(PC104-PadP$60)") (class "Default")
      (node (ref "PC104") (pin "P$60") (pinfunction "P$60_P$60") (pintype "bidirectional"))
    )
    (net (code "172") (name "unconnected-(PC104-PadP$61)") (class "Default")
      (node (ref "PC104") (pin "P$61") (pinfunction "P$61_P$61") (pintype "bidirectional"))
    )
    (net (code "173") (name "unconnected-(PC104-PadP$62)") (class "Default")
      (node (ref "PC104") (pin "P$62") (pinfunction "P$62_P$62") (pintype "bidirectional"))
    )
    (net (code "174") (name "unconnected-(PC104-PadP$63)") (class "Default")
      (node (ref "PC104") (pin "P$63") (pinfunction "P$63_P$63") (pintype "bidirectional"))
    )
    (net (code "175") (name "unconnected-(PC104-PadP$64)") (class "Default")
      (node (ref "PC104") (pin "P$64") (pinfunction "P$64_P$64") (pintype "bidirectional"))
    )
    (net (code "176") (name "unconnected-(PC104-PadP$65)") (class "Default")
      (node (ref "PC104") (pin "P$65") (pinfunction "P$65_P$65") (pintype "bidirectional"))
    )
    (net (code "177") (name "unconnected-(PC104-PadP$66)") (class "Default")
      (node (ref "PC104") (pin "P$66") (pinfunction "P$66_P$66") (pintype "bidirectional"))
    )
    (net (code "178") (name "unconnected-(PC104-PadP$67)") (class "Default")
      (node (ref "PC104") (pin "P$67") (pinfunction "P$67_P$67") (pintype "bidirectional"))
    )
    (net (code "179") (name "unconnected-(PC104-PadP$68)") (class "Default")
      (node (ref "PC104") (pin "P$68") (pinfunction "P$68_P$68") (pintype "bidirectional"))
    )
    (net (code "180") (name "unconnected-(PC104-PadP$73)") (class "Default")
      (node (ref "PC104") (pin "P$73") (pinfunction "P$73_P$73") (pintype "bidirectional"))
    )
    (net (code "181") (name "unconnected-(PC104-PadP$74)") (class "Default")
      (node (ref "PC104") (pin "P$74") (pinfunction "P$74_P$74") (pintype "bidirectional"))
    )
    (net (code "182") (name "unconnected-(PC104-PadP$75)") (class "Default")
      (node (ref "PC104") (pin "P$75") (pinfunction "P$75_P$75") (pintype "bidirectional"))
    )
    (net (code "183") (name "unconnected-(PC104-PadP$76)") (class "Default")
      (node (ref "PC104") (pin "P$76") (pinfunction "P$76_P$76") (pintype "bidirectional"))
    )
    (net (code "184") (name "unconnected-(PC104-PadP$81)") (class "Default")
      (node (ref "PC104") (pin "P$81") (pinfunction "P$81_P$81") (pintype "bidirectional"))
    )
    (net (code "185") (name "unconnected-(PC104-PadP$82)") (class "Default")
      (node (ref "PC104") (pin "P$82") (pinfunction "P$82_P$82") (pintype "bidirectional"))
    )
    (net (code "186") (name "unconnected-(PC104-PadP$83)") (class "Default")
      (node (ref "PC104") (pin "P$83") (pinfunction "P$83_P$83") (pintype "bidirectional"))
    )
    (net (code "187") (name "unconnected-(PC104-PadP$84)") (class "Default")
      (node (ref "PC104") (pin "P$84") (pinfunction "P$84_P$84") (pintype "bidirectional"))
    )
    (net (code "188") (name "unconnected-(PC104-PadP$89)") (class "Default")
      (node (ref "PC104") (pin "P$89") (pinfunction "P$89_P$89") (pintype "bidirectional"))
    )
    (net (code "189") (name "unconnected-(PC104-PadP$90)") (class "Default")
      (node (ref "PC104") (pin "P$90") (pinfunction "P$90_P$90") (pintype "bidirectional"))
    )
    (net (code "190") (name "unconnected-(PC104-PadP$91)") (class "Default")
      (node (ref "PC104") (pin "P$91") (pinfunction "P$91_P$91") (pintype "bidirectional"))
    )
    (net (code "191") (name "unconnected-(PC104-PadP$92)") (class "Default")
      (node (ref "PC104") (pin "P$92") (pinfunction "P$92_P$92") (pintype "bidirectional"))
    )
    (net (code "192") (name "unconnected-(PC104-PadP$95)") (class "Default")
      (node (ref "PC104") (pin "P$95") (pinfunction "P$95_P$95") (pintype "bidirectional"))
    )
    (net (code "193") (name "unconnected-(PC104-PadP$96)") (class "Default")
      (node (ref "PC104") (pin "P$96") (pinfunction "P$96_P$96") (pintype "bidirectional"))
    )
    (net (code "194") (name "unconnected-(PC104-RAHS_GND-PadP$94)") (class "Default")
      (node (ref "PC104") (pin "P$94") (pinfunction "RAHS_GND_P$94") (pintype "bidirectional"))
    )
    (net (code "195") (name "unconnected-(PC104-RAHS_VBAT-PadP$93)") (class "Default")
      (node (ref "PC104") (pin "P$93") (pinfunction "RAHS_VBAT_P$93") (pintype "bidirectional"))
    )
    (net (code "196") (name "unconnected-(PC104-TOPDEPLOY+-PadP$51)") (class "Default")
      (node (ref "PC104") (pin "P$51") (pinfunction "TOPDEPLOY+_P$51") (pintype "bidirectional"))
    )
    (net (code "197") (name "unconnected-(PC104-TOPDEPLOY+-PadP$55)") (class "Default")
      (node (ref "PC104") (pin "P$55") (pinfunction "TOPDEPLOY+_P$55") (pintype "bidirectional"))
    )
    (net (code "198") (name "unconnected-(PC104-TOPDEPLOY-$52-PadP$52)") (class "Default")
      (node (ref "PC104") (pin "P$52") (pinfunction "TOPDEPLOY-$52_P$52") (pintype "bidirectional"))
    )
    (net (code "199") (name "unconnected-(PC104-TOPDEPLOY-$56-PadP$56)") (class "Default")
      (node (ref "PC104") (pin "P$56") (pinfunction "TOPDEPLOY-$56_P$56") (pintype "bidirectional"))
    )
    (net (code "200") (name "unconnected-(U$3-P2.3_SPI-CS2-PadP2.4_SPI-CS2)") (class "Default")
      (node (ref "U$3") (pin "P2.4_SPI-CS2") (pinfunction "P2.3_SPI-CS2_P2.4_SPI-CS2") (pintype "bidirectional"))
    )
    (net (code "201") (name "unconnected-(U$3-PadP1.0_A0)") (class "Default")
      (node (ref "U$3") (pin "P1.0_A0") (pinfunction "P1.0_A0_P1.0_A0") (pintype "bidirectional"))
    )
    (net (code "202") (name "unconnected-(U$3-PadP1.1_A1)") (class "Default")
      (node (ref "U$3") (pin "P1.1_A1") (pinfunction "P1.1_A1_P1.1_A1") (pintype "bidirectional"))
    )
    (net (code "203") (name "unconnected-(U$3-PadP1.2_A2)") (class "Default")
      (node (ref "U$3") (pin "P1.2_A2") (pinfunction "P1.2_A2_P1.2_A2") (pintype "bidirectional"))
    )
    (net (code "204") (name "unconnected-(U$3-PadP1.3_A3)") (class "Default")
      (node (ref "U$3") (pin "P1.3_A3") (pinfunction "P1.3_A3_P1.3_A3") (pintype "bidirectional"))
    )
    (net (code "205") (name "unconnected-(U$3-PadP1.4_A4)") (class "Default")
      (node (ref "U$3") (pin "P1.4_A4") (pinfunction "P1.4_A4_P1.4_A4") (pintype "bidirectional"))
    )
    (net (code "206") (name "unconnected-(U$3-PadP1.5_A5)") (class "Default")
      (node (ref "U$3") (pin "P1.5_A5") (pinfunction "P1.5_A5_P1.5_A5") (pintype "bidirectional"))
    )
    (net (code "207") (name "unconnected-(U$3-PadP2.2_GPIO{slash}PWM)") (class "Default")
      (node (ref "U$3") (pin "P2.2_GPIO/PWM") (pinfunction "P2.2_GPIO/PWM_P2.2_GPIO/PWM") (pintype "bidirectional"))
    )
    (net (code "208") (name "unconnected-(U$3-PadP2.7_SPI-CS3)") (class "Default")
      (node (ref "U$3") (pin "P2.7_SPI-CS3") (pinfunction "P2.7_SPI-CS3_P2.7_SPI-CS3") (pintype "bidirectional"))
    )
    (net (code "209") (name "unconnected-(U$3-PadP3.0_A12)") (class "Default")
      (node (ref "U$3") (pin "P3.0_A12") (pinfunction "P3.0_A12_P3.0_A12") (pintype "bidirectional"))
    )
    (net (code "210") (name "unconnected-(U$3-PadP3.1_A13)") (class "Default")
      (node (ref "U$3") (pin "P3.1_A13") (pinfunction "P3.1_A13_P3.1_A13") (pintype "bidirectional"))
    )
    (net (code "211") (name "unconnected-(U$3-PadP3.2_A14)") (class "Default")
      (node (ref "U$3") (pin "P3.2_A14") (pinfunction "P3.2_A14_P3.2_A14") (pintype "bidirectional"))
    )
    (net (code "212") (name "unconnected-(U$3-PadP3.3_A15)") (class "Default")
      (node (ref "U$3") (pin "P3.3_A15") (pinfunction "P3.3_A15_P3.3_A15") (pintype "bidirectional"))
    )
    (net (code "213") (name "unconnected-(U$3-PadP4.1_GPIO)") (class "Default")
      (node (ref "U$3") (pin "P4.1_GPIO") (pinfunction "P4.1_GPIO_P4.1_GPIO") (pintype "bidirectional"))
    )
    (net (code "214") (name "unconnected-(U$3-PadP4.2_GPIO)") (class "Default")
      (node (ref "U$3") (pin "P4.2_GPIO") (pinfunction "P4.2_GPIO_P4.2_GPIO") (pintype "bidirectional"))
    )
    (net (code "215") (name "unconnected-(U$3-PadP5.0_I2C-SDA-1)") (class "Default")
      (node (ref "U$3") (pin "P5.0_I2C-SDA-1") (pinfunction "P5.0_I2C-SDA-1_P5.0_I2C-SDA-1") (pintype "bidirectional"))
    )
    (net (code "216") (name "unconnected-(U$3-PadP5.1_I2C-SCL-1)") (class "Default")
      (node (ref "U$3") (pin "P5.1_I2C-SCL-1") (pinfunction "P5.1_I2C-SCL-1_P5.1_I2C-SCL-1") (pintype "bidirectional"))
    )
    (net (code "217") (name "unconnected-(U$3-PadP5.4_SPI-MOSI)") (class "Default")
      (node (ref "U$3") (pin "P5.4_SPI-MOSI") (pinfunction "P5.4_SPI-MOSI_P5.4_SPI-MOSI") (pintype "bidirectional"))
    )
    (net (code "218") (name "unconnected-(U$3-PadP5.5_SPI-MISO)") (class "Default")
      (node (ref "U$3") (pin "P5.5_SPI-MISO") (pinfunction "P5.5_SPI-MISO_P5.5_SPI-MISO") (pintype "bidirectional"))
    )
    (net (code "219") (name "unconnected-(U$3-PadP5.6_SPI-CLK)") (class "Default")
      (node (ref "U$3") (pin "P5.6_SPI-CLK") (pinfunction "P5.6_SPI-CLK_P5.6_SPI-CLK") (pintype "bidirectional"))
    )
    (net (code "220") (name "unconnected-(U$3-PadP7.0_I2C-SDA-2)") (class "Default")
      (node (ref "U$3") (pin "P7.0_I2C-SDA-2") (pinfunction "P7.0_I2C-SDA-2_P7.0_I2C-SDA-2") (pintype "bidirectional"))
    )
    (net (code "221") (name "unconnected-(U$3-PadP7.1_I2C-SCL-2)") (class "Default")
      (node (ref "U$3") (pin "P7.1_I2C-SCL-2") (pinfunction "P7.1_I2C-SCL-2_P7.1_I2C-SCL-2") (pintype "bidirectional"))
    )
    (net (code "222") (name "unconnected-(U$6-NC-PadP$2)") (class "Default")
      (node (ref "U$6") (pin "P$2") (pinfunction "NC_P$2") (pintype "bidirectional"))
    )
    (net (code "223") (name "unconnected-(U$10-P2.3_SPI-CS2-PadP2.4_SPI-CS2)") (class "Default")
      (node (ref "U$10") (pin "P2.4_SPI-CS2") (pinfunction "P2.3_SPI-CS2_P2.4_SPI-CS2") (pintype "bidirectional"))
    )
    (net (code "224") (name "unconnected-(U$10-PadP1.0_A0)") (class "Default")
      (node (ref "U$10") (pin "P1.0_A0") (pinfunction "P1.0_A0_P1.0_A0") (pintype "bidirectional"))
    )
    (net (code "225") (name "unconnected-(U$10-PadP1.1_A1)") (class "Default")
      (node (ref "U$10") (pin "P1.1_A1") (pinfunction "P1.1_A1_P1.1_A1") (pintype "bidirectional"))
    )
    (net (code "226") (name "unconnected-(U$10-PadP1.2_A2)") (class "Default")
      (node (ref "U$10") (pin "P1.2_A2") (pinfunction "P1.2_A2_P1.2_A2") (pintype "bidirectional"))
    )
    (net (code "227") (name "unconnected-(U$10-PadP1.3_A3)") (class "Default")
      (node (ref "U$10") (pin "P1.3_A3") (pinfunction "P1.3_A3_P1.3_A3") (pintype "bidirectional"))
    )
    (net (code "228") (name "unconnected-(U$10-PadP1.4_A4)") (class "Default")
      (node (ref "U$10") (pin "P1.4_A4") (pinfunction "P1.4_A4_P1.4_A4") (pintype "bidirectional"))
    )
    (net (code "229") (name "unconnected-(U$10-PadP1.5_A5)") (class "Default")
      (node (ref "U$10") (pin "P1.5_A5") (pinfunction "P1.5_A5_P1.5_A5") (pintype "bidirectional"))
    )
    (net (code "230") (name "unconnected-(U$10-PadP2.2_GPIO{slash}PWM)") (class "Default")
      (node (ref "U$10") (pin "P2.2_GPIO/PWM") (pinfunction "P2.2_GPIO/PWM_P2.2_GPIO/PWM") (pintype "bidirectional"))
    )
    (net (code "231") (name "unconnected-(U$10-PadP2.7_SPI-CS3)") (class "Default")
      (node (ref "U$10") (pin "P2.7_SPI-CS3") (pinfunction "P2.7_SPI-CS3_P2.7_SPI-CS3") (pintype "bidirectional"))
    )
    (net (code "232") (name "unconnected-(U$10-PadP3.0_A12)") (class "Default")
      (node (ref "U$10") (pin "P3.0_A12") (pinfunction "P3.0_A12_P3.0_A12") (pintype "bidirectional"))
    )
    (net (code "233") (name "unconnected-(U$10-PadP3.1_A13)") (class "Default")
      (node (ref "U$10") (pin "P3.1_A13") (pinfunction "P3.1_A13_P3.1_A13") (pintype "bidirectional"))
    )
    (net (code "234") (name "unconnected-(U$10-PadP3.2_A14)") (class "Default")
      (node (ref "U$10") (pin "P3.2_A14") (pinfunction "P3.2_A14_P3.2_A14") (pintype "bidirectional"))
    )
    (net (code "235") (name "unconnected-(U$10-PadP3.3_A15)") (class "Default")
      (node (ref "U$10") (pin "P3.3_A15") (pinfunction "P3.3_A15_P3.3_A15") (pintype "bidirectional"))
    )
    (net (code "236") (name "unconnected-(U$10-PadP4.1_GPIO)") (class "Default")
      (node (ref "U$10") (pin "P4.1_GPIO") (pinfunction "P4.1_GPIO_P4.1_GPIO") (pintype "bidirectional"))
    )
    (net (code "237") (name "unconnected-(U$10-PadP4.2_GPIO)") (class "Default")
      (node (ref "U$10") (pin "P4.2_GPIO") (pinfunction "P4.2_GPIO_P4.2_GPIO") (pintype "bidirectional"))
    )
    (net (code "238") (name "unconnected-(U$10-PadP5.0_I2C-SDA-1)") (class "Default")
      (node (ref "U$10") (pin "P5.0_I2C-SDA-1") (pinfunction "P5.0_I2C-SDA-1_P5.0_I2C-SDA-1") (pintype "bidirectional"))
    )
    (net (code "239") (name "unconnected-(U$10-PadP5.1_I2C-SCL-1)") (class "Default")
      (node (ref "U$10") (pin "P5.1_I2C-SCL-1") (pinfunction "P5.1_I2C-SCL-1_P5.1_I2C-SCL-1") (pintype "bidirectional"))
    )
    (net (code "240") (name "unconnected-(U$10-PadP5.4_SPI-MOSI)") (class "Default")
      (node (ref "U$10") (pin "P5.4_SPI-MOSI") (pinfunction "P5.4_SPI-MOSI_P5.4_SPI-MOSI") (pintype "bidirectional"))
    )
    (net (code "241") (name "unconnected-(U$10-PadP5.5_SPI-MISO)") (class "Default")
      (node (ref "U$10") (pin "P5.5_SPI-MISO") (pinfunction "P5.5_SPI-MISO_P5.5_SPI-MISO") (pintype "bidirectional"))
    )
    (net (code "242") (name "unconnected-(U$10-PadP5.6_SPI-CLK)") (class "Default")
      (node (ref "U$10") (pin "P5.6_SPI-CLK") (pinfunction "P5.6_SPI-CLK_P5.6_SPI-CLK") (pintype "bidirectional"))
    )
    (net (code "243") (name "unconnected-(U$10-PadP7.0_I2C-SDA-2)") (class "Default")
      (node (ref "U$10") (pin "P7.0_I2C-SDA-2") (pinfunction "P7.0_I2C-SDA-2_P7.0_I2C-SDA-2") (pintype "bidirectional"))
    )
    (net (code "244") (name "unconnected-(U$10-PadP7.1_I2C-SCL-2)") (class "Default")
      (node (ref "U$10") (pin "P7.1_I2C-SCL-2") (pinfunction "P7.1_I2C-SCL-2_P7.1_I2C-SCL-2") (pintype "bidirectional"))
    )
    (net (code "245") (name "unconnected-(U$13-P2.3_SPI-CS2-PadP2.4_SPI-CS2)") (class "Default")
      (node (ref "U$13") (pin "P2.4_SPI-CS2") (pinfunction "P2.3_SPI-CS2_P2.4_SPI-CS2") (pintype "bidirectional"))
    )
    (net (code "246") (name "unconnected-(U$13-PadP1.0_A0)") (class "Default")
      (node (ref "U$13") (pin "P1.0_A0") (pinfunction "P1.0_A0_P1.0_A0") (pintype "bidirectional"))
    )
    (net (code "247") (name "unconnected-(U$13-PadP1.1_A1)") (class "Default")
      (node (ref "U$13") (pin "P1.1_A1") (pinfunction "P1.1_A1_P1.1_A1") (pintype "bidirectional"))
    )
    (net (code "248") (name "unconnected-(U$13-PadP1.2_A2)") (class "Default")
      (node (ref "U$13") (pin "P1.2_A2") (pinfunction "P1.2_A2_P1.2_A2") (pintype "bidirectional"))
    )
    (net (code "249") (name "unconnected-(U$13-PadP1.3_A3)") (class "Default")
      (node (ref "U$13") (pin "P1.3_A3") (pinfunction "P1.3_A3_P1.3_A3") (pintype "bidirectional"))
    )
    (net (code "250") (name "unconnected-(U$13-PadP1.4_A4)") (class "Default")
      (node (ref "U$13") (pin "P1.4_A4") (pinfunction "P1.4_A4_P1.4_A4") (pintype "bidirectional"))
    )
    (net (code "251") (name "unconnected-(U$13-PadP1.5_A5)") (class "Default")
      (node (ref "U$13") (pin "P1.5_A5") (pinfunction "P1.5_A5_P1.5_A5") (pintype "bidirectional"))
    )
    (net (code "252") (name "unconnected-(U$13-PadP2.2_GPIO{slash}PWM)") (class "Default")
      (node (ref "U$13") (pin "P2.2_GPIO/PWM") (pinfunction "P2.2_GPIO/PWM_P2.2_GPIO/PWM") (pintype "bidirectional"))
    )
    (net (code "253") (name "unconnected-(U$13-PadP2.7_SPI-CS3)") (class "Default")
      (node (ref "U$13") (pin "P2.7_SPI-CS3") (pinfunction "P2.7_SPI-CS3_P2.7_SPI-CS3") (pintype "bidirectional"))
    )
    (net (code "254") (name "unconnected-(U$13-PadP3.0_A12)") (class "Default")
      (node (ref "U$13") (pin "P3.0_A12") (pinfunction "P3.0_A12_P3.0_A12") (pintype "bidirectional"))
    )
    (net (code "255") (name "unconnected-(U$13-PadP3.1_A13)") (class "Default")
      (node (ref "U$13") (pin "P3.1_A13") (pinfunction "P3.1_A13_P3.1_A13") (pintype "bidirectional"))
    )
    (net (code "256") (name "unconnected-(U$13-PadP3.2_A14)") (class "Default")
      (node (ref "U$13") (pin "P3.2_A14") (pinfunction "P3.2_A14_P3.2_A14") (pintype "bidirectional"))
    )
    (net (code "257") (name "unconnected-(U$13-PadP3.3_A15)") (class "Default")
      (node (ref "U$13") (pin "P3.3_A15") (pinfunction "P3.3_A15_P3.3_A15") (pintype "bidirectional"))
    )
    (net (code "258") (name "unconnected-(U$13-PadP4.1_GPIO)") (class "Default")
      (node (ref "U$13") (pin "P4.1_GPIO") (pinfunction "P4.1_GPIO_P4.1_GPIO") (pintype "bidirectional"))
    )
    (net (code "259") (name "unconnected-(U$13-PadP4.2_GPIO)") (class "Default")
      (node (ref "U$13") (pin "P4.2_GPIO") (pinfunction "P4.2_GPIO_P4.2_GPIO") (pintype "bidirectional"))
    )
    (net (code "260") (name "unconnected-(U$13-PadP5.0_I2C-SDA-1)") (class "Default")
      (node (ref "U$13") (pin "P5.0_I2C-SDA-1") (pinfunction "P5.0_I2C-SDA-1_P5.0_I2C-SDA-1") (pintype "bidirectional"))
    )
    (net (code "261") (name "unconnected-(U$13-PadP5.1_I2C-SCL-1)") (class "Default")
      (node (ref "U$13") (pin "P5.1_I2C-SCL-1") (pinfunction "P5.1_I2C-SCL-1_P5.1_I2C-SCL-1") (pintype "bidirectional"))
    )
    (net (code "262") (name "unconnected-(U$13-PadP5.4_SPI-MOSI)") (class "Default")
      (node (ref "U$13") (pin "P5.4_SPI-MOSI") (pinfunction "P5.4_SPI-MOSI_P5.4_SPI-MOSI") (pintype "bidirectional"))
    )
    (net (code "263") (name "unconnected-(U$13-PadP5.5_SPI-MISO)") (class "Default")
      (node (ref "U$13") (pin "P5.5_SPI-MISO") (pinfunction "P5.5_SPI-MISO_P5.5_SPI-MISO") (pintype "bidirectional"))
    )
    (net (code "264") (name "unconnected-(U$13-PadP5.6_SPI-CLK)") (class "Default")
      (node (ref "U$13") (pin "P5.6_SPI-CLK") (pinfunction "P5.6_SPI-CLK_P5.6_SPI-CLK") (pintype "bidirectional"))
    )
    (net (code "265") (name "unconnected-(U$13-PadP7.0_I2C-SDA-2)") (class "Default")
      (node (ref "U$13") (pin "P7.0_I2C-SDA-2") (pinfunction "P7.0_I2C-SDA-2_P7.0_I2C-SDA-2") (pintype "bidirectional"))
    )
    (net (code "266") (name "unconnected-(U$13-PadP7.1_I2C-SCL-2)") (class "Default")
      (node (ref "U$13") (pin "P7.1_I2C-SCL-2") (pinfunction "P7.1_I2C-SCL-2_P7.1_I2C-SCL-2") (pintype "bidirectional"))
    )
  )
)
